# ACB_Jr_r_02.net
KiCad netlist of a schematic drawn in EAGLE
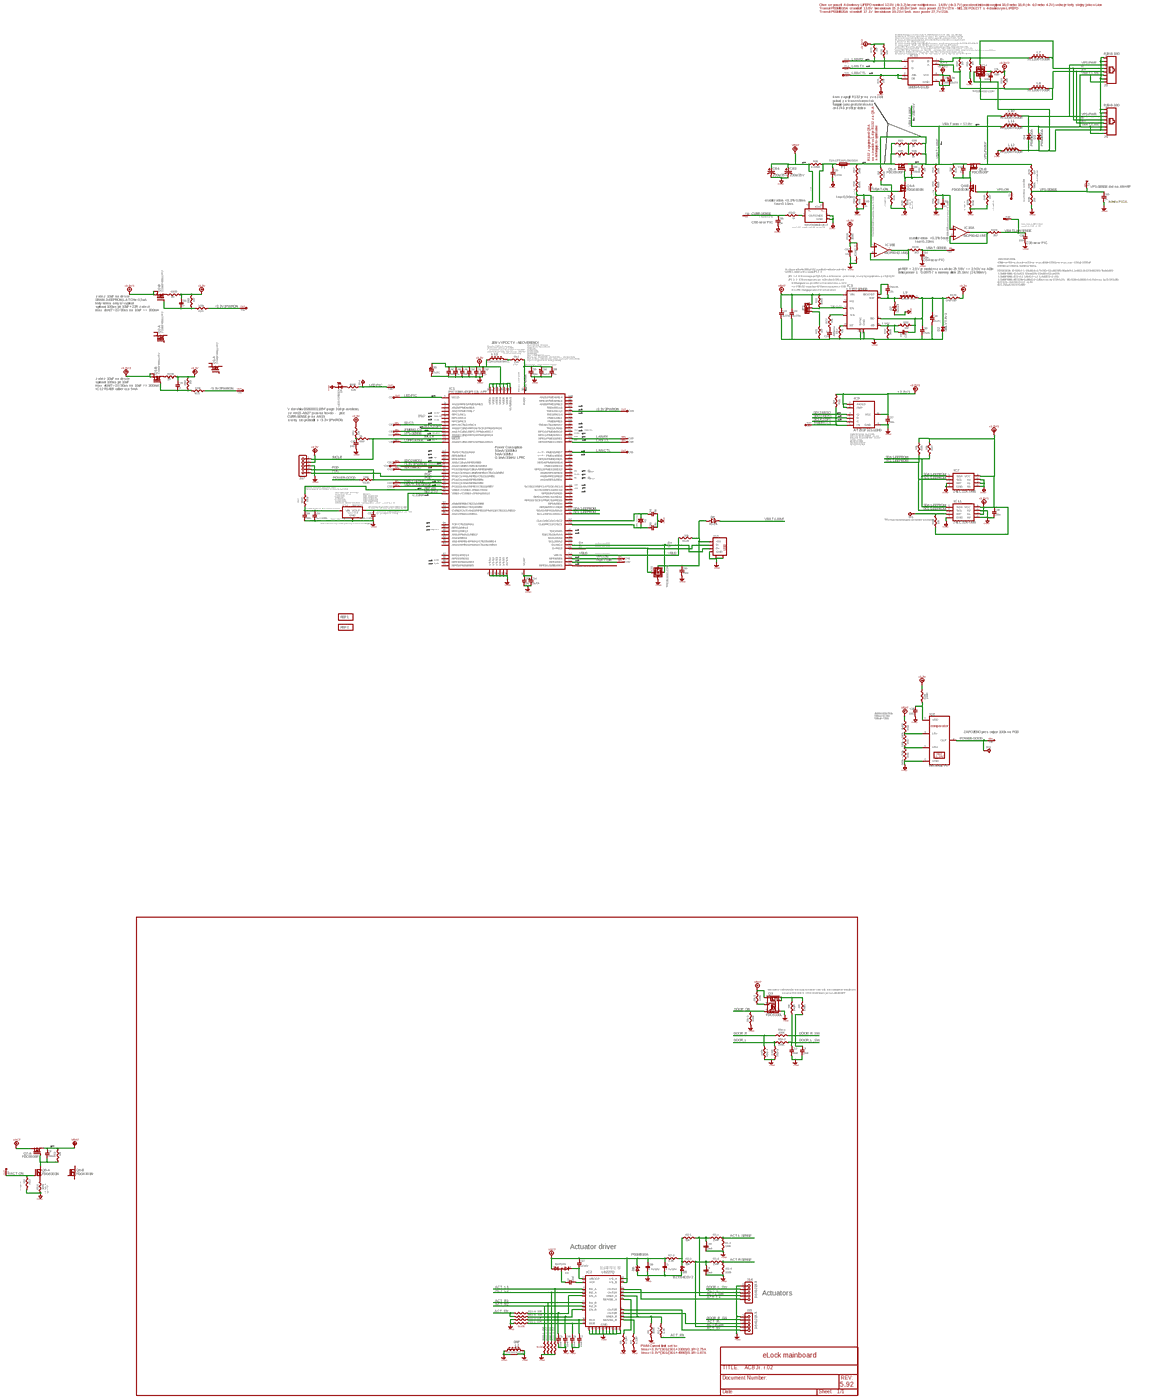
[diagram p0: schematic, sheet 1, overview]
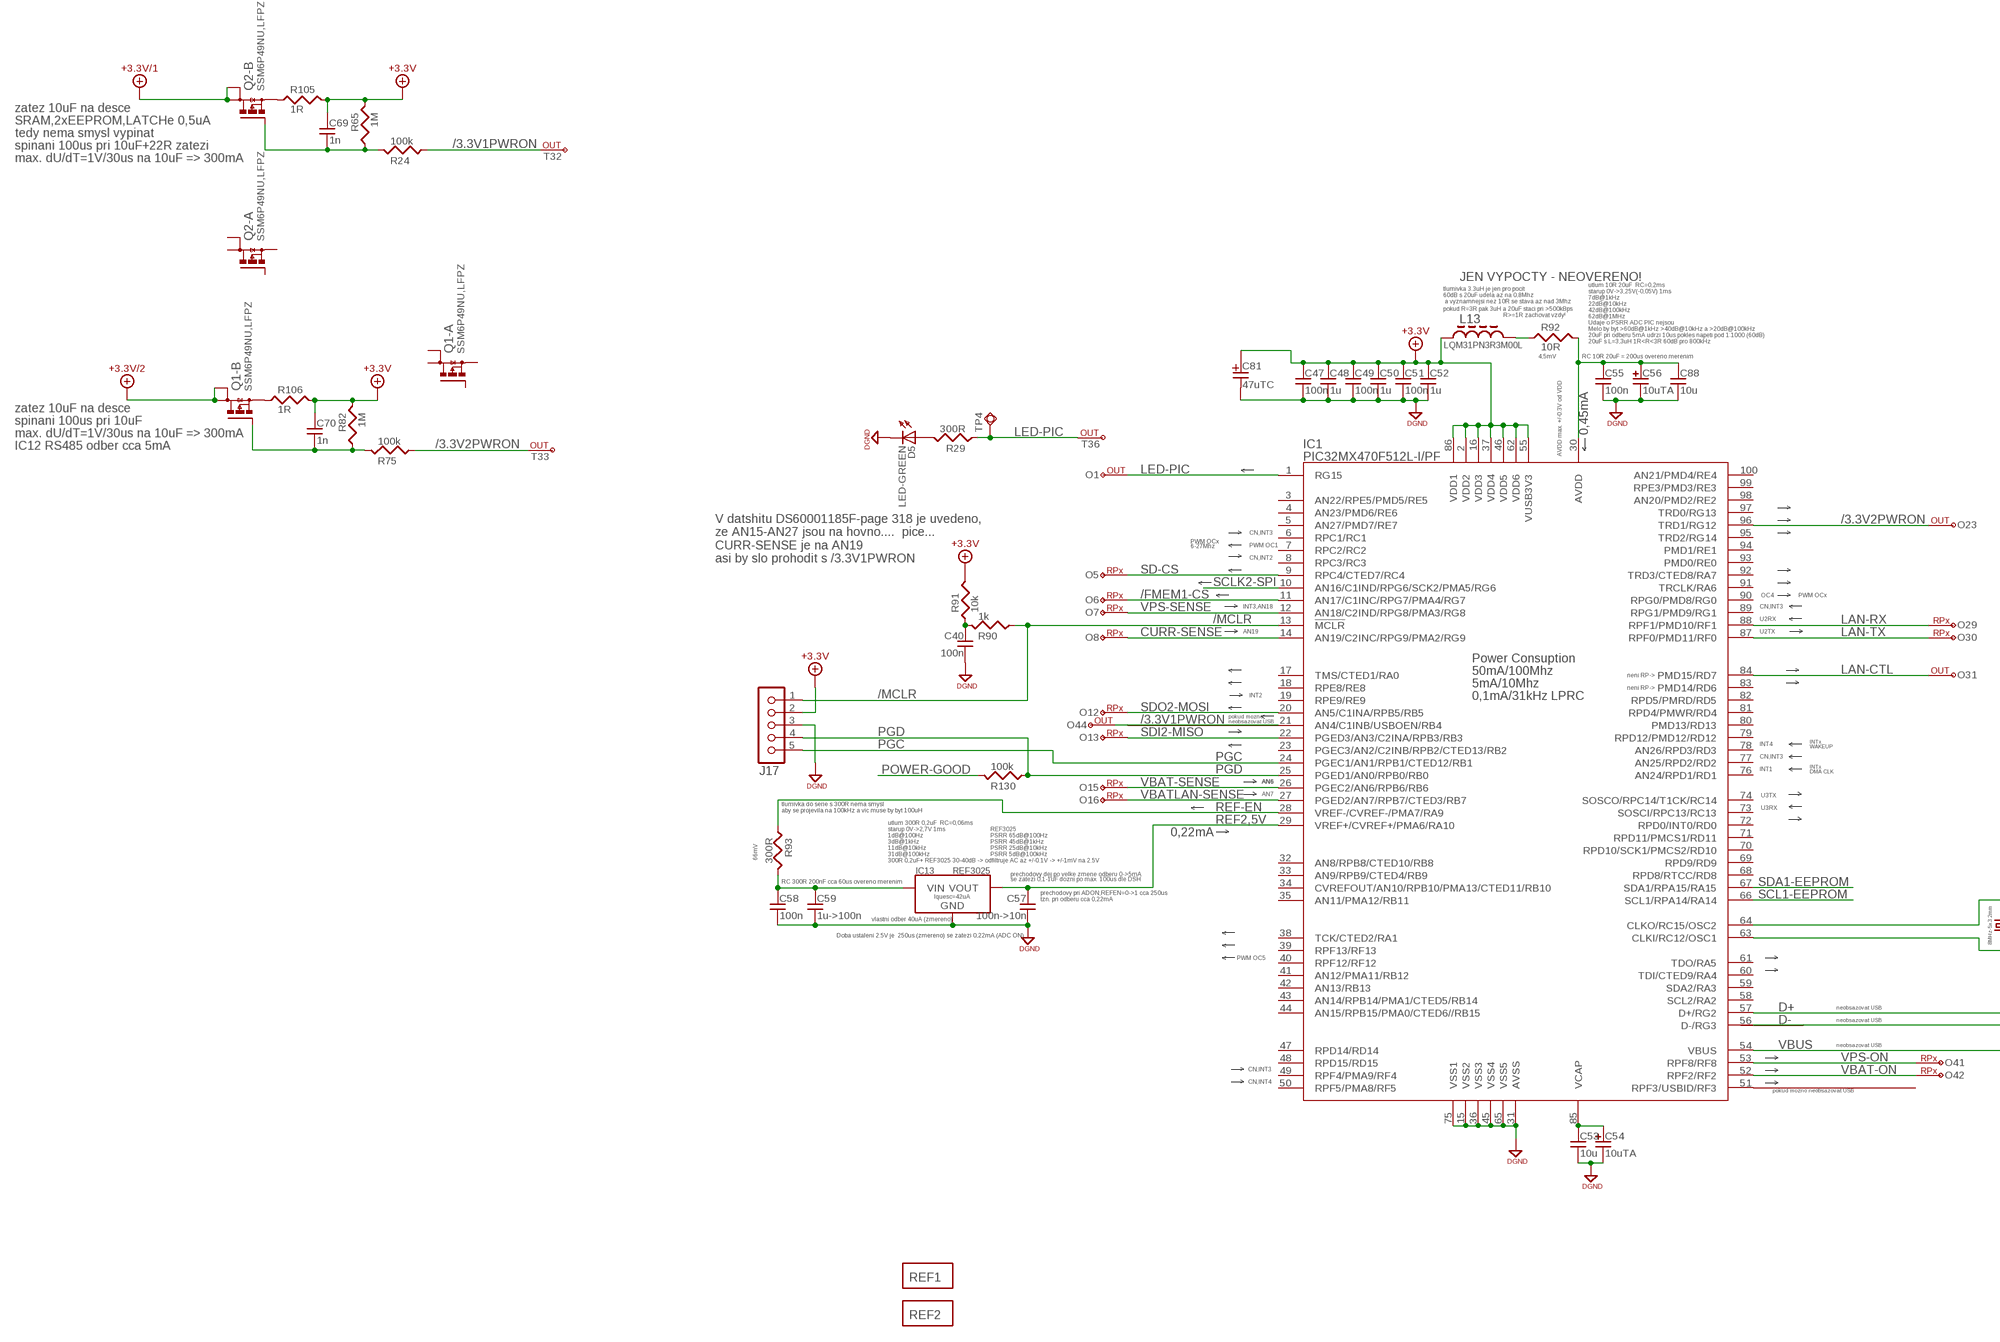
[diagram p1: schematic, sheet 1, part 1 of 5]
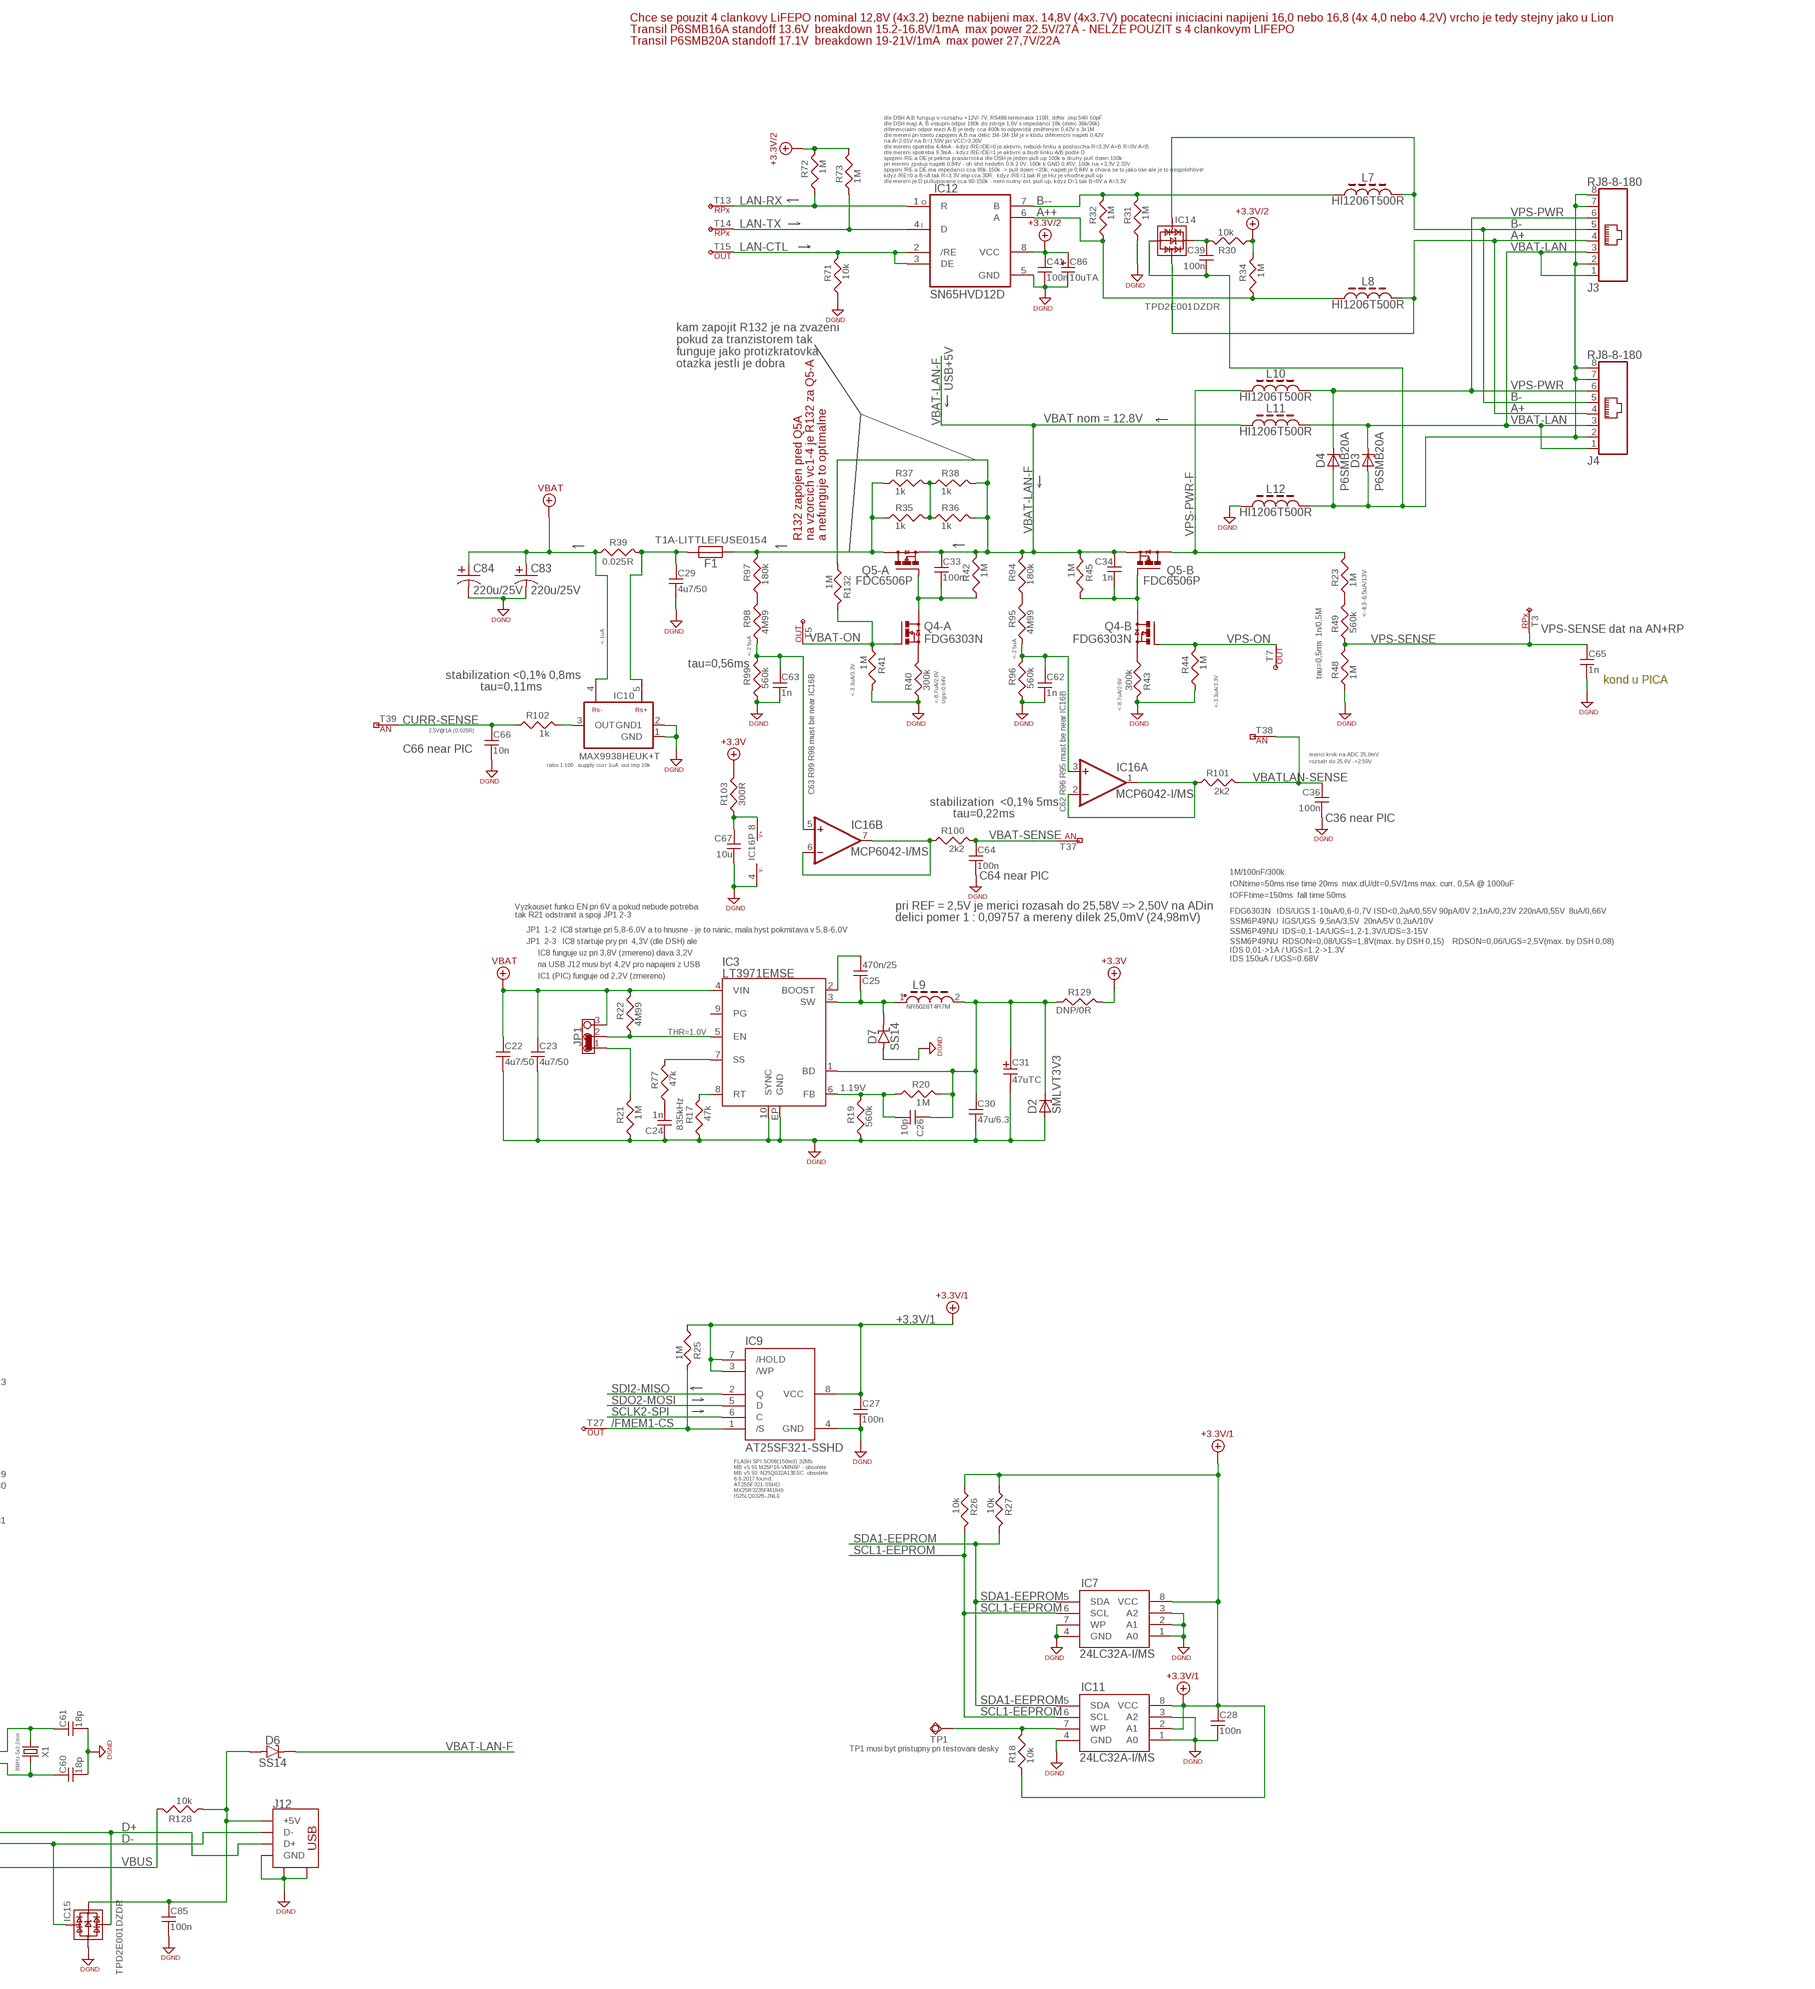
[diagram p2: schematic, sheet 1, part 2 of 5]
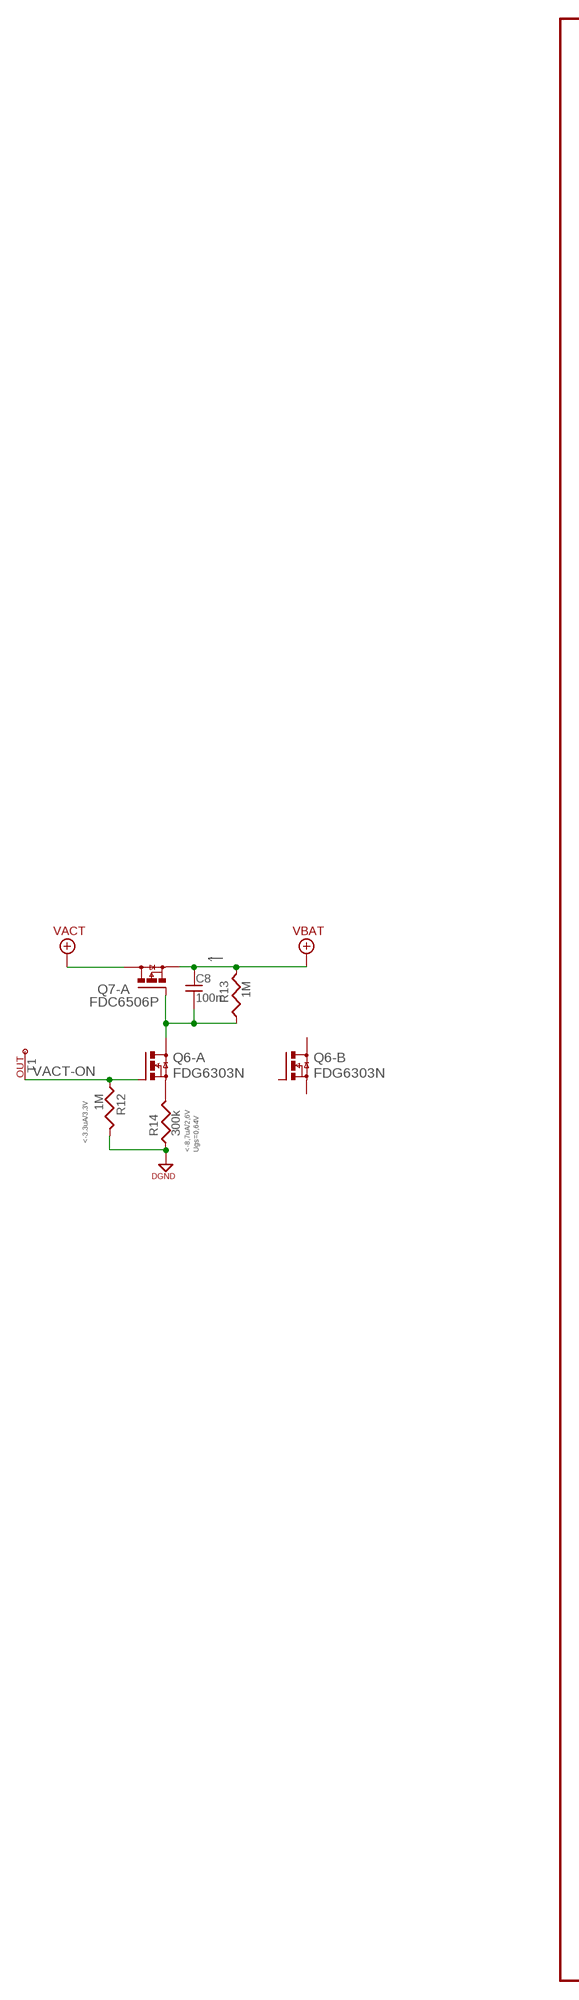
[diagram p3: schematic, sheet 1, part 3 of 5]
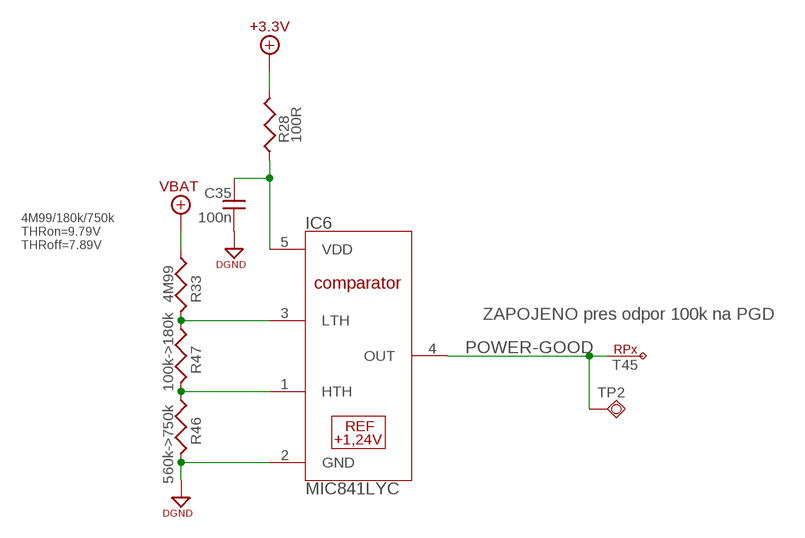
[diagram p4: schematic, sheet 1, part 4 of 5]
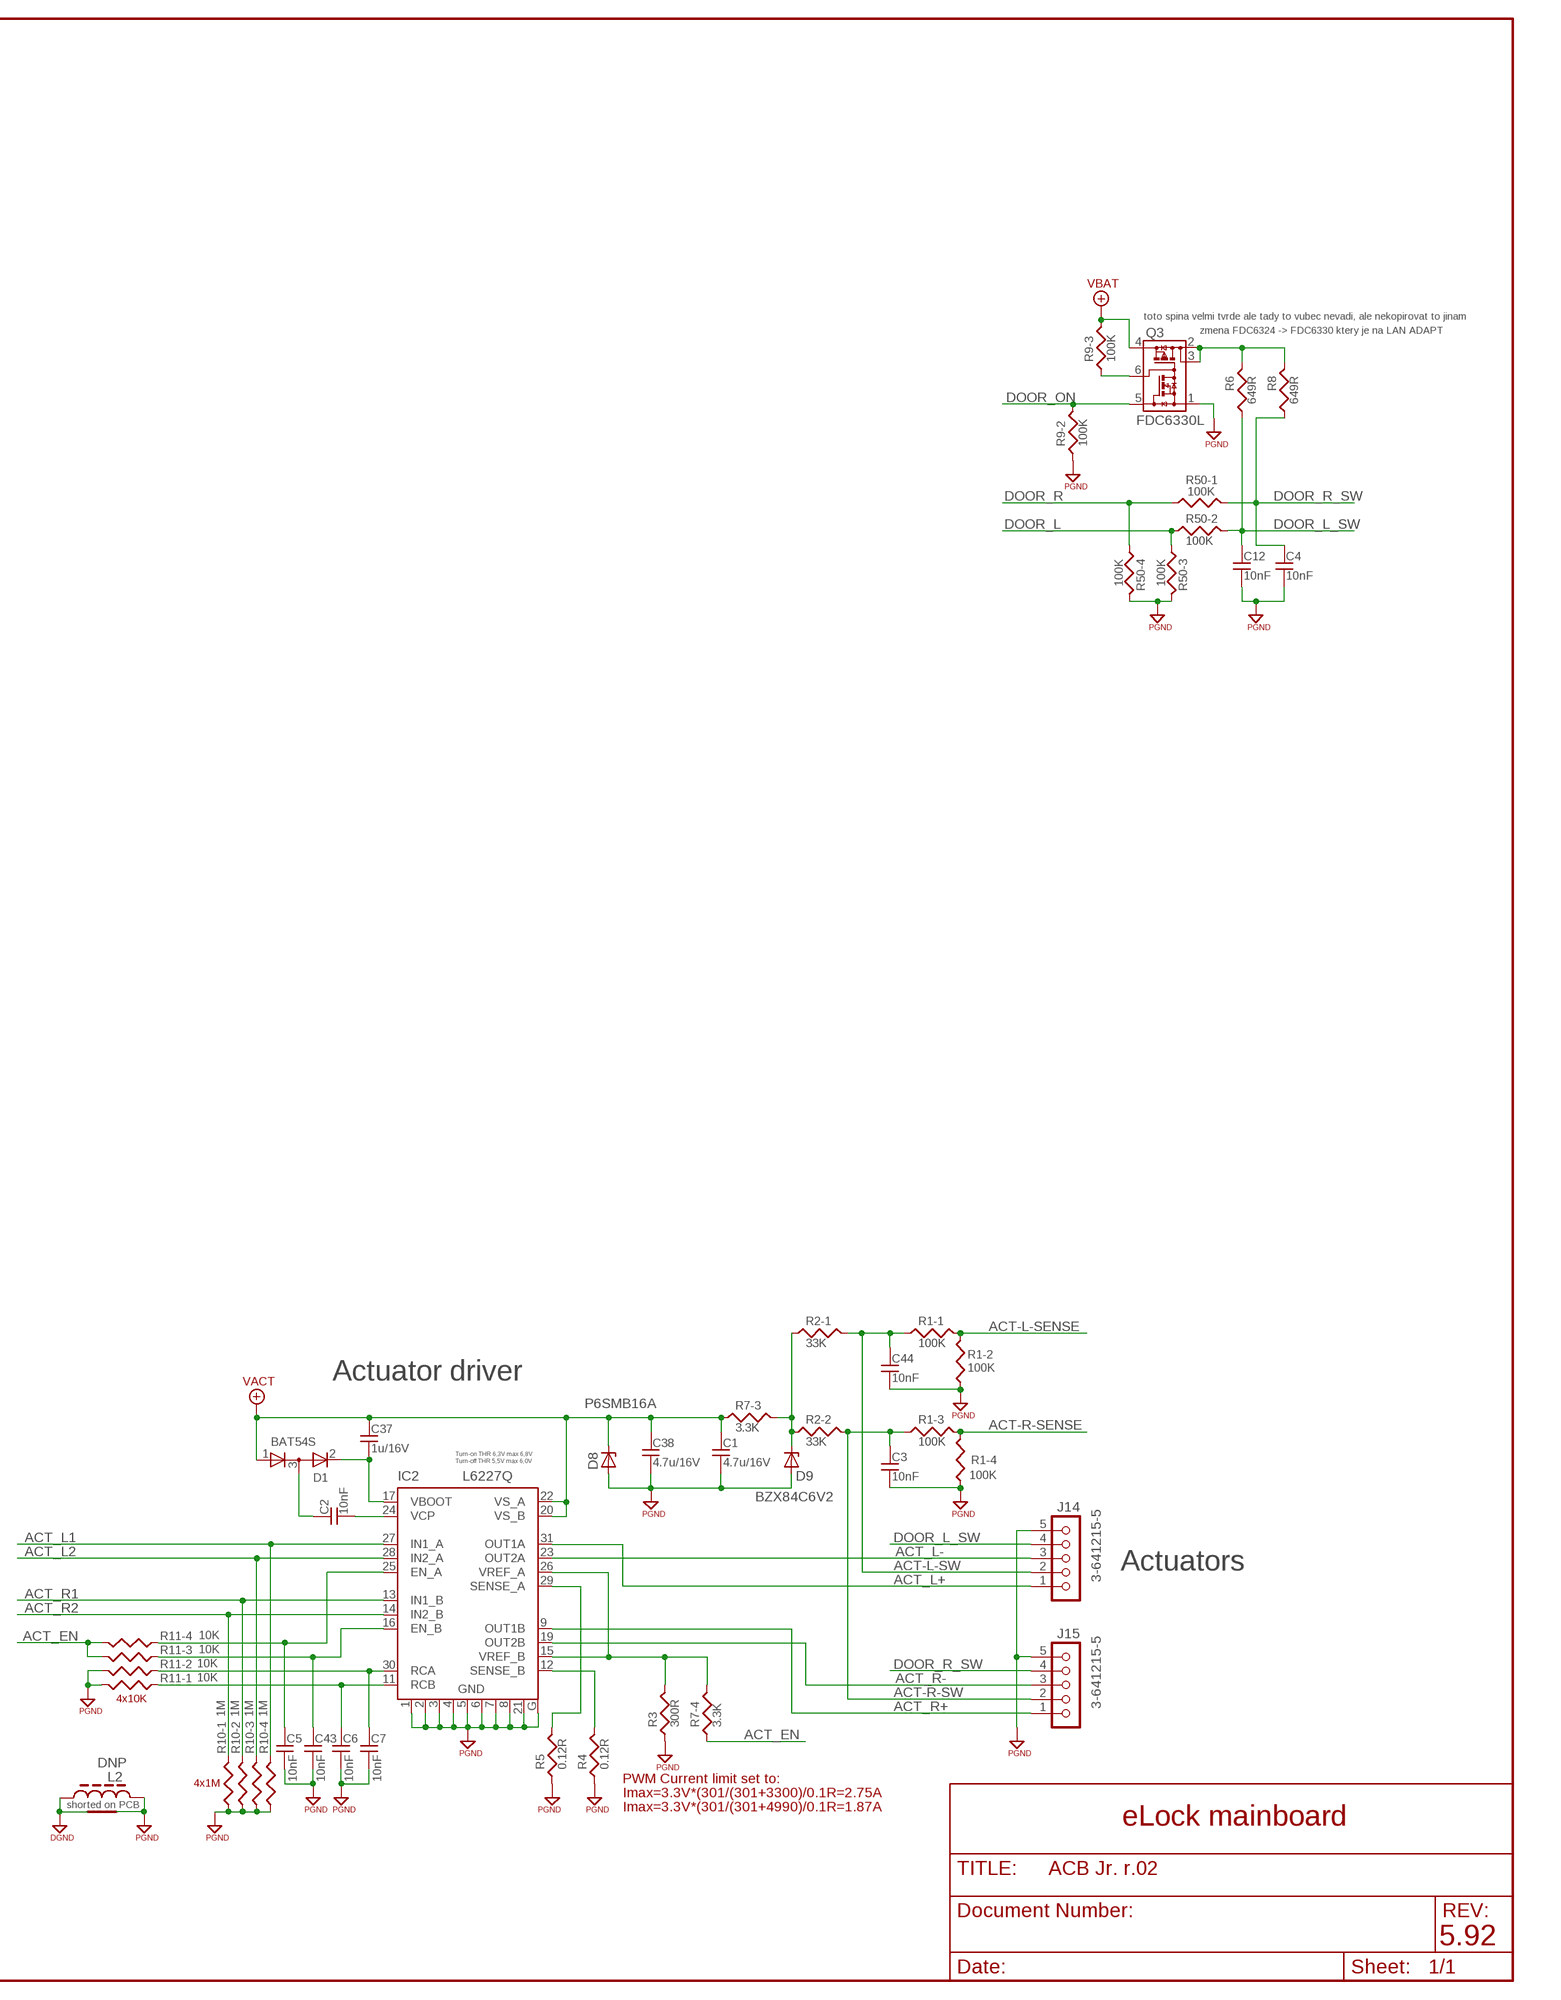
[diagram p5: schematic, sheet 1, part 5 of 5]

(export (version "E")
  (design (tool "Eeschema 10.0.6"))
  (components
    (comp (ref "C1")
      (value "4.7u/16V")
      (footprint "eagle-import:0805")
      (libsource (lib "eagle-import") (part "C-0805"))
    )
    (comp (ref "C2")
      (value "10nF")
      (footprint "eagle-import:0603")
      (libsource (lib "eagle-import") (part "C-0603"))
    )
    (comp (ref "C3")
      (value "10nF")
      (footprint "eagle-import:0603")
      (libsource (lib "eagle-import") (part "C-0603"))
    )
    (comp (ref "C4")
      (value "10nF")
      (footprint "eagle-import:0603")
      (libsource (lib "eagle-import") (part "C-0603"))
    )
    (comp (ref "C5")
      (value "10nF")
      (footprint "eagle-import:0603")
      (libsource (lib "eagle-import") (part "C-0603"))
    )
    (comp (ref "C6")
      (value "10nF")
      (footprint "eagle-import:0603")
      (libsource (lib "eagle-import") (part "C-0603"))
    )
    (comp (ref "C7")
      (value "10nF")
      (footprint "eagle-import:0603")
      (libsource (lib "eagle-import") (part "C-0603"))
    )
    (comp (ref "C8")
      (value "100n")
      (footprint "eagle-import:0603")
      (libsource (lib "eagle-import") (part "C-0603"))
    )
    (comp (ref "C12")
      (value "10nF")
      (footprint "eagle-import:0603")
      (libsource (lib "eagle-import") (part "C-0603"))
    )
    (comp (ref "C22")
      (value "4u7/50")
      (footprint "eagle-import:1206")
      (libsource (lib "eagle-import") (part "C-1206"))
    )
    (comp (ref "C23")
      (value "4u7/50")
      (footprint "eagle-import:1206")
      (libsource (lib "eagle-import") (part "C-1206"))
    )
    (comp (ref "C24")
      (value "1n")
      (footprint "eagle-import:0603")
      (libsource (lib "eagle-import") (part "C-0603"))
    )
    (comp (ref "C25")
      (value "470n/25")
      (footprint "eagle-import:0603")
      (libsource (lib "eagle-import") (part "C-0603"))
    )
    (comp (ref "C26")
      (value "10p")
      (footprint "eagle-import:0603")
      (libsource (lib "eagle-import") (part "C-0603"))
    )
    (comp (ref "C27")
      (value "100n")
      (footprint "eagle-import:0603")
      (libsource (lib "eagle-import") (part "C-0603"))
    )
    (comp (ref "C28")
      (value "100n")
      (footprint "eagle-import:0603")
      (libsource (lib "eagle-import") (part "C-0603"))
    )
    (comp (ref "C29")
      (value "4u7/50")
      (footprint "eagle-import:1206")
      (libsource (lib "eagle-import") (part "C-1206"))
    )
    (comp (ref "C30")
      (value "47u/6.3")
      (footprint "eagle-import:1206")
      (libsource (lib "eagle-import") (part "C-1206"))
    )
    (comp (ref "C31")
      (value "47uTC")
      (footprint "eagle-import:CT-C")
      (libsource (lib "eagle-import") (part "CT-C"))
    )
    (comp (ref "C33")
      (value "100n")
      (footprint "eagle-import:0603")
      (libsource (lib "eagle-import") (part "C-0603"))
    )
    (comp (ref "C34")
      (value "1n")
      (footprint "eagle-import:0603")
      (libsource (lib "eagle-import") (part "C-0603"))
    )
    (comp (ref "C35")
      (value "100n")
      (footprint "eagle-import:0603")
      (libsource (lib "eagle-import") (part "C-0603"))
    )
    (comp (ref "C36")
      (value "100n")
      (footprint "eagle-import:0603")
      (libsource (lib "eagle-import") (part "C-0603"))
    )
    (comp (ref "C37")
      (value "1u/16V")
      (footprint "eagle-import:0603")
      (libsource (lib "eagle-import") (part "C-0603"))
    )
    (comp (ref "C38")
      (value "4.7u/16V")
      (footprint "eagle-import:0805")
      (libsource (lib "eagle-import") (part "C-0805"))
    )
    (comp (ref "C39")
      (value "100n")
      (footprint "eagle-import:0603")
      (libsource (lib "eagle-import") (part "C-0603"))
    )
    (comp (ref "C40")
      (value "100n")
      (footprint "eagle-import:0603")
      (libsource (lib "eagle-import") (part "C-0603"))
    )
    (comp (ref "C41")
      (value "100n")
      (footprint "eagle-import:0603")
      (libsource (lib "eagle-import") (part "C-0603"))
    )
    (comp (ref "C43")
      (value "10nF")
      (footprint "eagle-import:0603")
      (libsource (lib "eagle-import") (part "C-0603"))
    )
    (comp (ref "C44")
      (value "10nF")
      (footprint "eagle-import:0603")
      (libsource (lib "eagle-import") (part "C-0603"))
    )
    (comp (ref "C47")
      (value "100n")
      (footprint "eagle-import:0603")
      (libsource (lib "eagle-import") (part "C-0603"))
    )
    (comp (ref "C48")
      (value "1u")
      (footprint "eagle-import:0603")
      (libsource (lib "eagle-import") (part "C-0603"))
    )
    (comp (ref "C49")
      (value "100n")
      (footprint "eagle-import:0603")
      (libsource (lib "eagle-import") (part "C-0603"))
    )
    (comp (ref "C50")
      (value "1u")
      (footprint "eagle-import:0603")
      (libsource (lib "eagle-import") (part "C-0603"))
    )
    (comp (ref "C51")
      (value "100n")
      (footprint "eagle-import:0603")
      (libsource (lib "eagle-import") (part "C-0603"))
    )
    (comp (ref "C52")
      (value "1u")
      (footprint "eagle-import:0603")
      (libsource (lib "eagle-import") (part "C-0603"))
    )
    (comp (ref "C53")
      (value "10u")
      (footprint "eagle-import:0603")
      (libsource (lib "eagle-import") (part "C-0603"))
    )
    (comp (ref "C54")
      (value "10uTA")
      (footprint "eagle-import:1206-POL-C")
      (libsource (lib "eagle-import") (part "CT-1206"))
    )
    (comp (ref "C55")
      (value "100n")
      (footprint "eagle-import:0603")
      (libsource (lib "eagle-import") (part "C-0603"))
    )
    (comp (ref "C56")
      (value "10uTA")
      (footprint "eagle-import:1206-POL-C")
      (libsource (lib "eagle-import") (part "CT-1206"))
    )
    (comp (ref "C57")
      (value "100n->10n")
      (footprint "eagle-import:0603")
      (libsource (lib "eagle-import") (part "C-0603"))
    )
    (comp (ref "C58")
      (value "100n")
      (footprint "eagle-import:0603")
      (libsource (lib "eagle-import") (part "C-0603"))
    )
    (comp (ref "C59")
      (value "1u->100n")
      (footprint "eagle-import:0603")
      (libsource (lib "eagle-import") (part "C-0603"))
    )
    (comp (ref "C60")
      (value "18p")
      (footprint "eagle-import:0603")
      (libsource (lib "eagle-import") (part "C-0603"))
    )
    (comp (ref "C61")
      (value "18p")
      (footprint "eagle-import:0603")
      (libsource (lib "eagle-import") (part "C-0603"))
    )
    (comp (ref "C62")
      (value "1n")
      (footprint "eagle-import:0603")
      (libsource (lib "eagle-import") (part "C-0603"))
    )
    (comp (ref "C63")
      (value "1n")
      (footprint "eagle-import:0603")
      (libsource (lib "eagle-import") (part "C-0603"))
    )
    (comp (ref "C64")
      (value "100n")
      (footprint "eagle-import:0603")
      (libsource (lib "eagle-import") (part "C-0603"))
    )
    (comp (ref "C65")
      (value "1n")
      (footprint "eagle-import:0603")
      (libsource (lib "eagle-import") (part "C-0603"))
    )
    (comp (ref "C66")
      (value "10n")
      (footprint "eagle-import:0603")
      (libsource (lib "eagle-import") (part "C-0603"))
    )
    (comp (ref "C67")
      (value "10u")
      (footprint "eagle-import:0603")
      (libsource (lib "eagle-import") (part "C-0603"))
    )
    (comp (ref "C69")
      (value "1n")
      (footprint "eagle-import:0603")
      (libsource (lib "eagle-import") (part "C-0603"))
    )
    (comp (ref "C70")
      (value "1n")
      (footprint "eagle-import:0603")
      (libsource (lib "eagle-import") (part "C-0603"))
    )
    (comp (ref "C81")
      (value "47uTC")
      (footprint "eagle-import:CT-C")
      (libsource (lib "eagle-import") (part "CT-C"))
    )
    (comp (ref "C83")
      (value "220u/25V")
      (footprint "eagle-import:CAP_8MM_DIA_SMT")
      (libsource (lib "eagle-import") (part "CAP-ELEC-SMD-8MM"))
    )
    (comp (ref "C84")
      (value "220u/25V")
      (footprint "eagle-import:CAP_8MM_DIA_SMT")
      (libsource (lib "eagle-import") (part "CAP-ELEC-SMD-8MM"))
    )
    (comp (ref "C85")
      (value "100n")
      (footprint "eagle-import:0603")
      (libsource (lib "eagle-import") (part "C-0603"))
    )
    (comp (ref "C86")
      (value "10uTA")
      (footprint "eagle-import:1206-POL-C")
      (libsource (lib "eagle-import") (part "CT-1206"))
    )
    (comp (ref "C88")
      (value "10u")
      (footprint "eagle-import:0603")
      (libsource (lib "eagle-import") (part "C-0603"))
    )
    (comp (ref "D1")
      (value "BAT54S")
      (footprint "eagle-import:SOT-23")
      (libsource (lib "eagle-import") (part "BAT54S"))
    )
    (comp (ref "D2")
      (value "SMLVT3V3")
      (footprint "eagle-import:SMA")
      (libsource (lib "eagle-import") (part "SMLVT3V3"))
    )
    (comp (ref "D3")
      (value "P6SMB20A")
      (footprint "eagle-import:SMB")
      (libsource (lib "eagle-import") (part "P6SMB"))
    )
    (comp (ref "D4")
      (value "P6SMB20A")
      (footprint "eagle-import:SMB")
      (libsource (lib "eagle-import") (part "P6SMB"))
    )
    (comp (ref "D5")
      (value "LED-GREEN")
      (footprint "eagle-import:0805-POL-D")
      (libsource (lib "eagle-import") (part "LED-0805"))
    )
    (comp (ref "D6")
      (value "SS14")
      (footprint "eagle-import:SMA")
      (libsource (lib "eagle-import") (part "DS-SMA"))
    )
    (comp (ref "D7")
      (value "SS14")
      (footprint "eagle-import:SMA")
      (libsource (lib "eagle-import") (part "DS-SMA"))
    )
    (comp (ref "D8")
      (value "P6SMB16A")
      (footprint "eagle-import:SMB")
      (libsource (lib "eagle-import") (part "P6SMB"))
    )
    (comp (ref "D9")
      (value "BZX84C6V2")
      (footprint "eagle-import:SOT-23")
      (libsource (lib "eagle-import") (part "BZX84C6V2"))
    )
    (comp (ref "F1")
      (value "T1A-LITTLEFUSE0154")
      (footprint "eagle-import:LITTLEFUSE0154")
      (libsource (lib "eagle-import") (part "POJISTKA-LITTLEFUSE0154"))
    )
    (comp (ref "IC1")
      (value "PIC32MX470F512L-I/PF")
      (footprint "eagle-import:TQFP100_14X14_0,5MM")
      (libsource (lib "eagle-import") (part "PIC32MX470F512L-I/PF"))
    )
    (comp (ref "IC2")
      (value "L6227Q")
      (footprint "eagle-import:SQFP-S-5X5-32")
      (libsource (lib "eagle-import") (part "L6227Q"))
    )
    (comp (ref "IC3")
      (value "LT3971EMSE")
      (footprint "eagle-import:MSOP10EXP")
      (libsource (lib "eagle-import") (part "LT3971EMSE"))
    )
    (comp (ref "IC6")
      (value "MIC841LYC")
      (footprint "eagle-import:SC-70-5")
      (libsource (lib "eagle-import") (part "MIC841LYC"))
    )
    (comp (ref "IC7")
      (value "24LC32A-I/MS")
      (footprint "eagle-import:MSOP-08")
      (libsource (lib "eagle-import") (part "24-I/MS"))
    )
    (comp (ref "IC9")
      (value "AT25SF321-SSHD")
      (footprint "eagle-import:SO-08")
      (libsource (lib "eagle-import") (part "M25P16-VMN6P"))
    )
    (comp (ref "IC10")
      (value "MAX9938HEUK+T")
      (footprint "eagle-import:SOT23-5")
      (libsource (lib "eagle-import") (part "TSM9938HEUK+T"))
    )
    (comp (ref "IC11")
      (value "24LC32A-I/MS")
      (footprint "eagle-import:MSOP-08")
      (libsource (lib "eagle-import") (part "24-I/MS"))
    )
    (comp (ref "IC12")
      (value "SN65HVD12D")
      (footprint "eagle-import:SO08")
      (libsource (lib "eagle-import") (part "SN65HVD3082ED"))
    )
    (comp (ref "IC13")
      (value "REF3025")
      (footprint "eagle-import:SOT23")
      (libsource (lib "eagle-import") (part "REF3025"))
    )
    (comp (ref "IC14")
      (value "TPD2E001DZDR")
      (footprint "eagle-import:SOT-143")
      (libsource (lib "eagle-import") (part "SR05.TCT"))
    )
    (comp (ref "IC15")
      (value "TPD2E001DZDR")
      (footprint "eagle-import:SOT-143")
      (libsource (lib "eagle-import") (part "SR05.TCT"))
    )
    (comp (ref "IC16")
      (value "MCP6042-I/MS")
      (footprint "eagle-import:MSOP-08")
      (libsource (lib "eagle-import") (part "MCP6042-I/MS"))
    )
    (comp (ref "J3")
      (value "RJ8-8-180")
      (footprint "eagle-import:RJ8-8-180")
      (libsource (lib "eagle-import") (part "RJ8-8-180"))
    )
    (comp (ref "J4")
      (value "RJ8-8-180")
      (footprint "eagle-import:RJ8-8-180")
      (libsource (lib "eagle-import") (part "RJ8-8-180"))
    )
    (comp (ref "J12")
      (value "USB_A_180")
      (footprint "eagle-import:USB_B_180")
      (libsource (lib "eagle-import") (part "USB_B_180"))
    )
    (comp (ref "J14")
      (value "3-641215-5")
      (footprint "eagle-import:3-641215-5")
      (libsource (lib "eagle-import") (part "3-641215-5"))
    )
    (comp (ref "J15")
      (value "3-641215-5")
      (footprint "eagle-import:3-641215-5")
      (libsource (lib "eagle-import") (part "3-641215-5"))
    )
    (comp (ref "J17")
      (value "DNP-open-hole")
      (footprint "eagle-import:MA05-1")
      (libsource (lib "eagle-import") (part "MA05-1"))
    )
    (comp (ref "JP1")
      (value "JP3CLOSE12")
      (footprint "eagle-import:JP3CLOSE12")
      (libsource (lib "eagle-import") (part "JP3CLOSE12"))
    )
    (comp (ref "L2")
      (value "DNP")
      (footprint "eagle-import:0805-0RTOP")
      (libsource (lib "eagle-import") (part "L-0805-0R"))
    )
    (comp (ref "L7")
      (value "HI1206T500R")
      (footprint "eagle-import:1206")
      (libsource (lib "eagle-import") (part "L-1206"))
    )
    (comp (ref "L8")
      (value "HI1206T500R")
      (footprint "eagle-import:1206")
      (libsource (lib "eagle-import") (part "L-1206"))
    )
    (comp (ref "L9")
      (value "NR6028T4R7M")
      (footprint "eagle-import:NR6028")
      (libsource (lib "eagle-import") (part "NR6028"))
    )
    (comp (ref "L10")
      (value "HI1206T500R")
      (footprint "eagle-import:1206")
      (libsource (lib "eagle-import") (part "L-1206"))
    )
    (comp (ref "L11")
      (value "HI1206T500R")
      (footprint "eagle-import:1206")
      (libsource (lib "eagle-import") (part "L-1206"))
    )
    (comp (ref "L12")
      (value "HI1206T500R")
      (footprint "eagle-import:1206")
      (libsource (lib "eagle-import") (part "L-1206"))
    )
    (comp (ref "L13")
      (value "LQM31PN3R3M00L")
      (footprint "eagle-import:1206")
      (libsource (lib "eagle-import") (part "L-1206"))
    )
    (comp (ref "O1")
      (value "PIC-OUT")
      (footprint "eagle-import:TEMP-PAD")
      (libsource (lib "eagle-import") (part "PIC-OUT"))
    )
    (comp (ref "O5")
      (value "PIC-RPX")
      (footprint "eagle-import:TEMP-PAD")
      (libsource (lib "eagle-import") (part "PIC-RPX"))
    )
    (comp (ref "O6")
      (value "PIC-RPX")
      (footprint "eagle-import:TEMP-PAD")
      (libsource (lib "eagle-import") (part "PIC-RPX"))
    )
    (comp (ref "O7")
      (value "PIC-RPX")
      (footprint "eagle-import:TEMP-PAD")
      (libsource (lib "eagle-import") (part "PIC-RPX"))
    )
    (comp (ref "O8")
      (value "PIC-RPX")
      (footprint "eagle-import:TEMP-PAD")
      (libsource (lib "eagle-import") (part "PIC-RPX"))
    )
    (comp (ref "O12")
      (value "PIC-RPX")
      (footprint "eagle-import:TEMP-PAD")
      (libsource (lib "eagle-import") (part "PIC-RPX"))
    )
    (comp (ref "O13")
      (value "PIC-RPX")
      (footprint "eagle-import:TEMP-PAD")
      (libsource (lib "eagle-import") (part "PIC-RPX"))
    )
    (comp (ref "O15")
      (value "PIC-RPX")
      (footprint "eagle-import:TEMP-PAD")
      (libsource (lib "eagle-import") (part "PIC-RPX"))
    )
    (comp (ref "O16")
      (value "PIC-RPX")
      (footprint "eagle-import:TEMP-PAD")
      (libsource (lib "eagle-import") (part "PIC-RPX"))
    )
    (comp (ref "O23")
      (value "PIC-OUT")
      (footprint "eagle-import:TEMP-PAD")
      (libsource (lib "eagle-import") (part "PIC-OUT"))
    )
    (comp (ref "O29")
      (value "PIC-RPX")
      (footprint "eagle-import:TEMP-PAD")
      (libsource (lib "eagle-import") (part "PIC-RPX"))
    )
    (comp (ref "O30")
      (value "PIC-RPX")
      (footprint "eagle-import:TEMP-PAD")
      (libsource (lib "eagle-import") (part "PIC-RPX"))
    )
    (comp (ref "O31")
      (value "PIC-OUT")
      (footprint "eagle-import:TEMP-PAD")
      (libsource (lib "eagle-import") (part "PIC-OUT"))
    )
    (comp (ref "O41")
      (value "PIC-RPX")
      (footprint "eagle-import:TEMP-PAD")
      (libsource (lib "eagle-import") (part "PIC-RPX"))
    )
    (comp (ref "O42")
      (value "PIC-RPX")
      (footprint "eagle-import:TEMP-PAD")
      (libsource (lib "eagle-import") (part "PIC-RPX"))
    )
    (comp (ref "O44")
      (value "PIC-OUT")
      (footprint "eagle-import:TEMP-PAD")
      (libsource (lib "eagle-import") (part "PIC-OUT"))
    )
    (comp (ref "Q1")
      (value "SSM6P49NU,LFPZ")
      (footprint "eagle-import:MICRO_FET")
      (libsource (lib "eagle-import") (part "SSM6P49PZNU,LF"))
    )
    (comp (ref "Q2")
      (value "SSM6P49NU,LFPZ")
      (footprint "eagle-import:MICRO_FET")
      (libsource (lib "eagle-import") (part "SSM6P49PZNU,LF"))
    )
    (comp (ref "Q3")
      (value "FDC6330L")
      (footprint "eagle-import:SSOT-6")
      (libsource (lib "eagle-import") (part "FDC6330L"))
    )
    (comp (ref "Q4")
      (value "FDG6303N")
      (footprint "eagle-import:SC70-6")
      (libsource (lib "eagle-import") (part "FDG6303N"))
    )
    (comp (ref "Q5")
      (value "FDC6506P")
      (footprint "eagle-import:SSOT-6")
      (libsource (lib "eagle-import") (part "FDC6506D"))
    )
    (comp (ref "Q6")
      (value "FDG6303N")
      (footprint "eagle-import:SC70-6")
      (libsource (lib "eagle-import") (part "FDG6303N"))
    )
    (comp (ref "Q7")
      (value "FDC6506P")
      (footprint "eagle-import:SSOT-6")
      (libsource (lib "eagle-import") (part "FDC6506D"))
    )
    (comp (ref "R1")
      (value "100K")
      (footprint "eagle-import:0603-ARRAY")
      (libsource (lib "eagle-import") (part "EXB-38"))
    )
    (comp (ref "R2")
      (value "33K")
      (footprint "eagle-import:0603-ARRAY")
      (libsource (lib "eagle-import") (part "EXB-38"))
    )
    (comp (ref "R3")
      (value "300R")
      (footprint "eagle-import:0603")
      (libsource (lib "eagle-import") (part "R-0603"))
    )
    (comp (ref "R4")
      (value "0.12R")
      (footprint "eagle-import:0805")
      (libsource (lib "eagle-import") (part "R-0805"))
    )
    (comp (ref "R5")
      (value "0.12R")
      (footprint "eagle-import:0805")
      (libsource (lib "eagle-import") (part "R-0805"))
    )
    (comp (ref "R6")
      (value "649R")
      (footprint "eagle-import:0603")
      (libsource (lib "eagle-import") (part "R-0603"))
    )
    (comp (ref "R7")
      (value "3.3K")
      (footprint "eagle-import:0603-ARRAY")
      (libsource (lib "eagle-import") (part "EXB-38"))
    )
    (comp (ref "R8")
      (value "649R")
      (footprint "eagle-import:0603")
      (libsource (lib "eagle-import") (part "R-0603"))
    )
    (comp (ref "R9")
      (value "100K")
      (footprint "eagle-import:0603-ARRAY")
      (libsource (lib "eagle-import") (part "EXB-38"))
    )
    (comp (ref "R10")
      (value "1M")
      (footprint "eagle-import:0603-ARRAY")
      (libsource (lib "eagle-import") (part "EXB-38"))
    )
    (comp (ref "R11")
      (value "10K")
      (footprint "eagle-import:0603-ARRAY")
      (libsource (lib "eagle-import") (part "EXB-38"))
    )
    (comp (ref "R12")
      (value "1M")
      (footprint "eagle-import:0603")
      (libsource (lib "eagle-import") (part "R-0603"))
    )
    (comp (ref "R13")
      (value "1M")
      (footprint "eagle-import:0603")
      (libsource (lib "eagle-import") (part "R-0603"))
    )
    (comp (ref "R14")
      (value "300k")
      (footprint "eagle-import:0603")
      (libsource (lib "eagle-import") (part "R-0603"))
    )
    (comp (ref "R17")
      (value "47k")
      (footprint "eagle-import:0603")
      (libsource (lib "eagle-import") (part "R-0603"))
    )
    (comp (ref "R18")
      (value "10k")
      (footprint "eagle-import:0603")
      (libsource (lib "eagle-import") (part "R-0603"))
    )
    (comp (ref "R19")
      (value "560k")
      (footprint "eagle-import:0603")
      (libsource (lib "eagle-import") (part "R-0603"))
    )
    (comp (ref "R20")
      (value "1M")
      (footprint "eagle-import:0603")
      (libsource (lib "eagle-import") (part "R-0603"))
    )
    (comp (ref "R21")
      (value "1M")
      (footprint "eagle-import:0603")
      (libsource (lib "eagle-import") (part "R-0603"))
    )
    (comp (ref "R22")
      (value "4M99")
      (footprint "eagle-import:0603")
      (libsource (lib "eagle-import") (part "R-0603"))
    )
    (comp (ref "R23")
      (value "1M")
      (footprint "eagle-import:0603")
      (libsource (lib "eagle-import") (part "R-0603"))
    )
    (comp (ref "R24")
      (value "100k")
      (footprint "eagle-import:0603")
      (libsource (lib "eagle-import") (part "R-0603"))
    )
    (comp (ref "R25")
      (value "1M")
      (footprint "eagle-import:0603")
      (libsource (lib "eagle-import") (part "R-0603"))
    )
    (comp (ref "R26")
      (value "10k")
      (footprint "eagle-import:0603")
      (libsource (lib "eagle-import") (part "R-0603"))
    )
    (comp (ref "R27")
      (value "10k")
      (footprint "eagle-import:0603")
      (libsource (lib "eagle-import") (part "R-0603"))
    )
    (comp (ref "R28")
      (value "100R")
      (footprint "eagle-import:0603")
      (libsource (lib "eagle-import") (part "R-0603"))
    )
    (comp (ref "R29")
      (value "300R")
      (footprint "eagle-import:0603")
      (libsource (lib "eagle-import") (part "R-0603"))
    )
    (comp (ref "R30")
      (value "10k")
      (footprint "eagle-import:0603")
      (libsource (lib "eagle-import") (part "R-0603"))
    )
    (comp (ref "R31")
      (value "1M")
      (footprint "eagle-import:0603")
      (libsource (lib "eagle-import") (part "R-0603"))
    )
    (comp (ref "R32")
      (value "1M")
      (footprint "eagle-import:0603")
      (libsource (lib "eagle-import") (part "R-0603"))
    )
    (comp (ref "R33")
      (value "4M99")
      (footprint "eagle-import:0603")
      (libsource (lib "eagle-import") (part "R-0603"))
    )
    (comp (ref "R34")
      (value "1M")
      (footprint "eagle-import:0603")
      (libsource (lib "eagle-import") (part "R-0603"))
    )
    (comp (ref "R35")
      (value "1k")
      (footprint "eagle-import:0805")
      (libsource (lib "eagle-import") (part "R-0805"))
    )
    (comp (ref "R36")
      (value "1k")
      (footprint "eagle-import:0805")
      (libsource (lib "eagle-import") (part "R-0805"))
    )
    (comp (ref "R37")
      (value "1k")
      (footprint "eagle-import:0805")
      (libsource (lib "eagle-import") (part "R-0805"))
    )
    (comp (ref "R38")
      (value "1k")
      (footprint "eagle-import:0805")
      (libsource (lib "eagle-import") (part "R-0805"))
    )
    (comp (ref "R39")
      (value "0.025R")
      (footprint "eagle-import:0805")
      (libsource (lib "eagle-import") (part "R-0805"))
    )
    (comp (ref "R40")
      (value "300k")
      (footprint "eagle-import:0603")
      (libsource (lib "eagle-import") (part "R-0603"))
    )
    (comp (ref "R41")
      (value "1M")
      (footprint "eagle-import:0603")
      (libsource (lib "eagle-import") (part "R-0603"))
    )
    (comp (ref "R42")
      (value "1M")
      (footprint "eagle-import:0603")
      (libsource (lib "eagle-import") (part "R-0603"))
    )
    (comp (ref "R43")
      (value "300k")
      (footprint "eagle-import:0603")
      (libsource (lib "eagle-import") (part "R-0603"))
    )
    (comp (ref "R44")
      (value "1M")
      (footprint "eagle-import:0603")
      (libsource (lib "eagle-import") (part "R-0603"))
    )
    (comp (ref "R45")
      (value "1M")
      (footprint "eagle-import:0603")
      (libsource (lib "eagle-import") (part "R-0603"))
    )
    (comp (ref "R46")
      (value "560k->750k")
      (footprint "eagle-import:0603")
      (libsource (lib "eagle-import") (part "R-0603"))
    )
    (comp (ref "R47")
      (value "100k->180k")
      (footprint "eagle-import:0603")
      (libsource (lib "eagle-import") (part "R-0603"))
    )
    (comp (ref "R48")
      (value "1M")
      (footprint "eagle-import:0603")
      (libsource (lib "eagle-import") (part "R-0603"))
    )
    (comp (ref "R49")
      (value "560k")
      (footprint "eagle-import:0603")
      (libsource (lib "eagle-import") (part "R-0603"))
    )
    (comp (ref "R50")
      (value "100K")
      (footprint "eagle-import:0603-ARRAY")
      (libsource (lib "eagle-import") (part "EXB-38"))
    )
    (comp (ref "R65")
      (value "1M")
      (footprint "eagle-import:0603")
      (libsource (lib "eagle-import") (part "R-0603"))
    )
    (comp (ref "R71")
      (value "10k")
      (footprint "eagle-import:0603")
      (libsource (lib "eagle-import") (part "R-0603"))
    )
    (comp (ref "R72")
      (value "1M")
      (footprint "eagle-import:0603")
      (libsource (lib "eagle-import") (part "R-0603"))
    )
    (comp (ref "R73")
      (value "1M")
      (footprint "eagle-import:0603")
      (libsource (lib "eagle-import") (part "R-0603"))
    )
    (comp (ref "R75")
      (value "100k")
      (footprint "eagle-import:0603")
      (libsource (lib "eagle-import") (part "R-0603"))
    )
    (comp (ref "R77")
      (value "47k")
      (footprint "eagle-import:0603")
      (libsource (lib "eagle-import") (part "R-0603"))
    )
    (comp (ref "R82")
      (value "1M")
      (footprint "eagle-import:0603")
      (libsource (lib "eagle-import") (part "R-0603"))
    )
    (comp (ref "R90")
      (value "1k")
      (footprint "eagle-import:0603")
      (libsource (lib "eagle-import") (part "R-0603"))
    )
    (comp (ref "R91")
      (value "10k")
      (footprint "eagle-import:0603")
      (libsource (lib "eagle-import") (part "R-0603"))
    )
    (comp (ref "R92")
      (value "10R")
      (footprint "eagle-import:0603")
      (libsource (lib "eagle-import") (part "R-0603"))
    )
    (comp (ref "R93")
      (value "300R")
      (footprint "eagle-import:0603")
      (libsource (lib "eagle-import") (part "R-0603"))
    )
    (comp (ref "R94")
      (value "180k")
      (footprint "eagle-import:0603")
      (libsource (lib "eagle-import") (part "R-0603"))
    )
    (comp (ref "R95")
      (value "4M99")
      (footprint "eagle-import:0603")
      (libsource (lib "eagle-import") (part "R-0603"))
    )
    (comp (ref "R96")
      (value "560k")
      (footprint "eagle-import:0603")
      (libsource (lib "eagle-import") (part "R-0603"))
    )
    (comp (ref "R97")
      (value "180k")
      (footprint "eagle-import:0603")
      (libsource (lib "eagle-import") (part "R-0603"))
    )
    (comp (ref "R98")
      (value "4M99")
      (footprint "eagle-import:0603")
      (libsource (lib "eagle-import") (part "R-0603"))
    )
    (comp (ref "R99")
      (value "560k")
      (footprint "eagle-import:0603")
      (libsource (lib "eagle-import") (part "R-0603"))
    )
    (comp (ref "R100")
      (value "2k2")
      (footprint "eagle-import:0603")
      (libsource (lib "eagle-import") (part "R-0603"))
    )
    (comp (ref "R101")
      (value "2k2")
      (footprint "eagle-import:0603")
      (libsource (lib "eagle-import") (part "R-0603"))
    )
    (comp (ref "R102")
      (value "1k")
      (footprint "eagle-import:0603")
      (libsource (lib "eagle-import") (part "R-0603"))
    )
    (comp (ref "R103")
      (value "300R")
      (footprint "eagle-import:0603")
      (libsource (lib "eagle-import") (part "R-0603"))
    )
    (comp (ref "R105")
      (value "1R")
      (footprint "eagle-import:0805")
      (libsource (lib "eagle-import") (part "R-0805"))
    )
    (comp (ref "R106")
      (value "1R")
      (footprint "eagle-import:0805")
      (libsource (lib "eagle-import") (part "R-0805"))
    )
    (comp (ref "R128")
      (value "10k")
      (footprint "eagle-import:0603")
      (libsource (lib "eagle-import") (part "R-0603"))
    )
    (comp (ref "R129")
      (value "DNP/0R")
      (footprint "eagle-import:0603")
      (libsource (lib "eagle-import") (part "R-0603"))
    )
    (comp (ref "R130")
      (value "100k")
      (footprint "eagle-import:0603")
      (libsource (lib "eagle-import") (part "R-0603"))
    )
    (comp (ref "R132")
      (value "1M")
      (footprint "eagle-import:0603")
      (libsource (lib "eagle-import") (part "R-0603"))
    )
    (comp (ref "REF1")
      (value "REF")
      (footprint "eagle-import:REF")
      (libsource (lib "eagle-import") (part "REF"))
    )
    (comp (ref "REF2")
      (value "REF")
      (footprint "eagle-import:REF")
      (libsource (lib "eagle-import") (part "REF"))
    )
    (comp (ref "T1")
      (value "PIC-OUT")
      (footprint "eagle-import:TEMP-PAD")
      (libsource (lib "eagle-import") (part "PIC-OUT"))
    )
    (comp (ref "T3")
      (value "PIC-RPX")
      (footprint "eagle-import:TEMP-PAD")
      (libsource (lib "eagle-import") (part "PIC-RPX"))
    )
    (comp (ref "T5")
      (value "PIC-OUT")
      (footprint "eagle-import:TEMP-PAD")
      (libsource (lib "eagle-import") (part "PIC-OUT"))
    )
    (comp (ref "T7")
      (value "PIC-OUT")
      (footprint "eagle-import:TEMP-PAD")
      (libsource (lib "eagle-import") (part "PIC-OUT"))
    )
    (comp (ref "T13")
      (value "PIC-RPX")
      (footprint "eagle-import:TEMP-PAD")
      (libsource (lib "eagle-import") (part "PIC-RPX"))
    )
    (comp (ref "T14")
      (value "PIC-RPX")
      (footprint "eagle-import:TEMP-PAD")
      (libsource (lib "eagle-import") (part "PIC-RPX"))
    )
    (comp (ref "T15")
      (value "PIC-OUT")
      (footprint "eagle-import:TEMP-PAD")
      (libsource (lib "eagle-import") (part "PIC-OUT"))
    )
    (comp (ref "T27")
      (value "PIC-OUT")
      (footprint "eagle-import:TEMP-PAD")
      (libsource (lib "eagle-import") (part "PIC-OUT"))
    )
    (comp (ref "T32")
      (value "PIC-OUT")
      (footprint "eagle-import:TEMP-PAD")
      (libsource (lib "eagle-import") (part "PIC-OUT"))
    )
    (comp (ref "T33")
      (value "PIC-OUT")
      (footprint "eagle-import:TEMP-PAD")
      (libsource (lib "eagle-import") (part "PIC-OUT"))
    )
    (comp (ref "T36")
      (value "PIC-OUT")
      (footprint "eagle-import:TEMP-PAD")
      (libsource (lib "eagle-import") (part "PIC-OUT"))
    )
    (comp (ref "T37")
      (value "PIN-AN")
      (footprint "eagle-import:TEMP-PAD")
      (libsource (lib "eagle-import") (part "PIN-AN"))
    )
    (comp (ref "T38")
      (value "PIN-AN")
      (footprint "eagle-import:TEMP-PAD")
      (libsource (lib "eagle-import") (part "PIN-AN"))
    )
    (comp (ref "T39")
      (value "PIN-AN")
      (footprint "eagle-import:TEMP-PAD")
      (libsource (lib "eagle-import") (part "PIN-AN"))
    )
    (comp (ref "T45")
      (value "PIC-RPX")
      (footprint "eagle-import:TEMP-PAD")
      (libsource (lib "eagle-import") (part "PIC-RPX"))
    )
    (comp (ref "TP1")
      (value "DNP-TestPoint")
      (footprint "eagle-import:SMD_ROUND_1MM")
      (libsource (lib "eagle-import") (part "ROUND_SMD1MM"))
    )
    (comp (ref "TP2")
      (value "DNP-TestPoint")
      (footprint "eagle-import:TH_ROUND_14MM08MM")
      (libsource (lib "eagle-import") (part "ROUND_SMDTH1.4MM"))
    )
    (comp (ref "TP4")
      (value "DNP-TestPoint")
      (footprint "eagle-import:TH_ROUND_14MM08MM")
      (libsource (lib "eagle-import") (part "ROUND_SMDTH1.4MM"))
    )
    (comp (ref "X1")
      (value "8MHz-5x3.2mm")
      (footprint "eagle-import:7B")
      (libsource (lib "eagle-import") (part "XTAL-7B"))
    )
  )
  (nets
    (net (code "1") (name "+3.3V") (class "Default")
      (node (ref "C47") (pin "1") (pinfunction "1_1") (pintype "passive"))
      (node (ref "C48") (pin "1") (pinfunction "1_1") (pintype "passive"))
      (node (ref "C49") (pin "1") (pinfunction "1_1") (pintype "passive"))
      (node (ref "C50") (pin "1") (pinfunction "1_1") (pintype "passive"))
      (node (ref "C51") (pin "1") (pinfunction "1_1") (pintype "passive"))
      (node (ref "C52") (pin "1") (pinfunction "1_1") (pintype "passive"))
      (node (ref "C69") (pin "1") (pinfunction "1_1") (pintype "passive"))
      (node (ref "C70") (pin "1") (pinfunction "1_1") (pintype "passive"))
      (node (ref "C81") (pin "+") (pinfunction "+_+") (pintype "passive"))
      (node (ref "IC1") (pin "16") (pinfunction "VDD3_16") (pintype "input"))
      (node (ref "IC1") (pin "2") (pinfunction "VDD2_2") (pintype "input"))
      (node (ref "IC1") (pin "37") (pinfunction "VDD4_37") (pintype "input"))
      (node (ref "IC1") (pin "46") (pinfunction "VDD5_46") (pintype "input"))
      (node (ref "IC1") (pin "55") (pinfunction "VUSB3V3_55") (pintype "input"))
      (node (ref "IC1") (pin "62") (pinfunction "VDD6_62") (pintype "input"))
      (node (ref "IC1") (pin "86") (pinfunction "VDD1_86") (pintype "input"))
      (node (ref "J17") (pin "2") (pinfunction "2_2") (pintype "passive"))
      (node (ref "L13") (pin "1") (pinfunction "1_1") (pintype "passive"))
      (node (ref "R103") (pin "2") (pinfunction "2_2") (pintype "passive"))
      (node (ref "R105") (pin "2") (pinfunction "2_2") (pintype "passive"))
      (node (ref "R106") (pin "2") (pinfunction "2_2") (pintype "passive"))
      (node (ref "R129") (pin "1") (pinfunction "1_1") (pintype "passive"))
      (node (ref "R28") (pin "2") (pinfunction "2_2") (pintype "passive"))
      (node (ref "R65") (pin "1") (pinfunction "1_1") (pintype "passive"))
      (node (ref "R82") (pin "1") (pinfunction "1_1") (pintype "passive"))
      (node (ref "R91") (pin "2") (pinfunction "2_2") (pintype "passive"))
    )
    (net (code "2") (name "+3.3V{slash}1") (class "Default")
      (node (ref "C27") (pin "1") (pinfunction "1_1") (pintype "passive"))
      (node (ref "C28") (pin "1") (pinfunction "1_1") (pintype "passive"))
      (node (ref "IC11") (pin "2") (pinfunction "A1_2") (pintype "input"))
      (node (ref "IC11") (pin "8") (pinfunction "VCC_8") (pintype "input"))
      (node (ref "IC7") (pin "8") (pinfunction "VCC_8") (pintype "input"))
      (node (ref "IC9") (pin "3") (pinfunction "/WP_3") (pintype "input"))
      (node (ref "IC9") (pin "7") (pinfunction "/HOLD_7") (pintype "input"))
      (node (ref "IC9") (pin "8") (pinfunction "VCC_8") (pintype "input"))
      (node (ref "Q2") (pin "3") (pinfunction "D_3") (pintype "passive"))
      (node (ref "Q2") (pin "P2") (pinfunction "D1_P2") (pintype "passive"))
      (node (ref "R18") (pin "1") (pinfunction "1_1") (pintype "passive"))
      (node (ref "R25") (pin "2") (pinfunction "2_2") (pintype "passive"))
      (node (ref "R26") (pin "1") (pinfunction "1_1") (pintype "passive"))
      (node (ref "R27") (pin "1") (pinfunction "1_1") (pintype "passive"))
    )
    (net (code "3") (name "+3.3V{slash}2") (class "Default")
      (node (ref "C41") (pin "1") (pinfunction "1_1") (pintype "passive"))
      (node (ref "C86") (pin "+") (pinfunction "+_+") (pintype "passive"))
      (node (ref "IC12") (pin "8") (pinfunction "VCC_8") (pintype "input"))
      (node (ref "Q1") (pin "3") (pinfunction "D_3") (pintype "passive"))
      (node (ref "Q1") (pin "P2") (pinfunction "D1_P2") (pintype "passive"))
      (node (ref "R30") (pin "2") (pinfunction "2_2") (pintype "passive"))
      (node (ref "R34") (pin "1") (pinfunction "1_1") (pintype "passive"))
      (node (ref "R72") (pin "1") (pinfunction "1_1") (pintype "passive"))
      (node (ref "R73") (pin "2") (pinfunction "2_2") (pintype "passive"))
    )
    (net (code "4") (name "/A+") (class "Default")
      (node (ref "IC14") (pin "3") (pinfunction "3_3") (pintype "passive"))
      (node (ref "J3") (pin "4") (pinfunction "4_4") (pintype "passive"))
      (node (ref "J4") (pin "4") (pinfunction "4_4") (pintype "passive"))
      (node (ref "L8") (pin "2") (pinfunction "2_2") (pintype "passive"))
    )
    (net (code "5") (name "/A++") (class "Default")
      (node (ref "IC12") (pin "6") (pinfunction "A_6") (pintype "bidirectional"))
      (node (ref "L8") (pin "1") (pinfunction "1_1") (pintype "passive"))
      (node (ref "R32") (pin "2") (pinfunction "2_2") (pintype "passive"))
      (node (ref "R34") (pin "2") (pinfunction "2_2") (pintype "passive"))
    )
    (net (code "6") (name "/ACT-L-SENSE") (class "Default")
      (node (ref "R1") (pin "7") (pinfunction "2_7") (pintype "passive"))
      (node (ref "R1") (pin "8") (pinfunction "2_8") (pintype "passive"))
    )
    (net (code "7") (name "/ACT-L-SW") (class "Default")
      (node (ref "C44") (pin "1") (pinfunction "1_1") (pintype "passive"))
      (node (ref "J14") (pin "2") (pinfunction "2_2") (pintype "passive"))
      (node (ref "R1") (pin "1") (pinfunction "1_1") (pintype "passive"))
      (node (ref "R2") (pin "8") (pinfunction "2_8") (pintype "passive"))
    )
    (net (code "8") (name "/ACT-R-SENSE") (class "Default")
      (node (ref "R1") (pin "5") (pinfunction "2_5") (pintype "passive"))
      (node (ref "R1") (pin "6") (pinfunction "2_6") (pintype "passive"))
    )
    (net (code "9") (name "/ACT-R-SW") (class "Default")
      (node (ref "C3") (pin "1") (pinfunction "1_1") (pintype "passive"))
      (node (ref "J15") (pin "2") (pinfunction "2_2") (pintype "passive"))
      (node (ref "R1") (pin "3") (pinfunction "1_3") (pintype "passive"))
      (node (ref "R2") (pin "7") (pinfunction "2_7") (pintype "passive"))
    )
    (net (code "10") (name "/ACT_EN") (class "Default")
      (node (ref "R11") (pin "5") (pinfunction "2_5") (pintype "passive"))
      (node (ref "R11") (pin "6") (pinfunction "2_6") (pintype "passive"))
      (node (ref "R7") (pin "4") (pinfunction "1_4") (pintype "passive"))
    )
    (net (code "11") (name "/ACT_L+") (class "Default")
      (node (ref "IC2") (pin "31") (pinfunction "OUT1A_31") (pintype "output"))
      (node (ref "J14") (pin "1") (pinfunction "1_1") (pintype "passive"))
    )
    (net (code "12") (name "/ACT_L-") (class "Default")
      (node (ref "IC2") (pin "23") (pinfunction "OUT2A_23") (pintype "output"))
      (node (ref "J14") (pin "3") (pinfunction "3_3") (pintype "passive"))
    )
    (net (code "13") (name "/ACT_L1") (class "Default")
      (node (ref "IC2") (pin "27") (pinfunction "IN1_A_27") (pintype "input"))
      (node (ref "R10") (pin "5") (pinfunction "2_5") (pintype "passive"))
    )
    (net (code "14") (name "/ACT_L2") (class "Default")
      (node (ref "IC2") (pin "28") (pinfunction "IN2_A_28") (pintype "input"))
      (node (ref "R10") (pin "6") (pinfunction "2_6") (pintype "passive"))
    )
    (net (code "15") (name "/ACT_R+") (class "Default")
      (node (ref "IC2") (pin "9") (pinfunction "OUT1B_9") (pintype "output"))
      (node (ref "J15") (pin "1") (pinfunction "1_1") (pintype "passive"))
    )
    (net (code "16") (name "/ACT_R-") (class "Default")
      (node (ref "IC2") (pin "19") (pinfunction "OUT2B_19") (pintype "output"))
      (node (ref "J15") (pin "3") (pinfunction "3_3") (pintype "passive"))
    )
    (net (code "17") (name "/ACT_R1") (class "Default")
      (node (ref "IC2") (pin "13") (pinfunction "IN1_B_13") (pintype "input"))
      (node (ref "R10") (pin "7") (pinfunction "2_7") (pintype "passive"))
    )
    (net (code "18") (name "/ACT_R2") (class "Default")
      (node (ref "IC2") (pin "14") (pinfunction "IN2_B_14") (pintype "input"))
      (node (ref "R10") (pin "8") (pinfunction "2_8") (pintype "passive"))
    )
    (net (code "19") (name "/B-") (class "Default")
      (node (ref "IC14") (pin "2") (pinfunction "2_2") (pintype "passive"))
      (node (ref "J3") (pin "5") (pinfunction "5_5") (pintype "passive"))
      (node (ref "J4") (pin "5") (pinfunction "5_5") (pintype "passive"))
      (node (ref "L7") (pin "2") (pinfunction "2_2") (pintype "passive"))
    )
    (net (code "20") (name "/B--") (class "Default")
      (node (ref "IC12") (pin "7") (pinfunction "B_7") (pintype "bidirectional"))
      (node (ref "L7") (pin "1") (pinfunction "1_1") (pintype "passive"))
      (node (ref "R31") (pin "1") (pinfunction "1_1") (pintype "passive"))
      (node (ref "R32") (pin "1") (pinfunction "1_1") (pintype "passive"))
    )
    (net (code "21") (name "/CURR-SENSE") (class "Default")
      (node (ref "C66") (pin "1") (pinfunction "1_1") (pintype "passive"))
      (node (ref "IC1") (pin "14") (pinfunction "AN19/C2INC/RPG9/PMA2/RG9_14") (pintype "bidirectional"))
      (node (ref "O8") (pin "P$1") (pinfunction "TP_P$1") (pintype "passive"))
      (node (ref "R102") (pin "2") (pinfunction "2_2") (pintype "passive"))
      (node (ref "T39") (pin "P$1") (pinfunction "TP_P$1") (pintype "passive"))
    )
    (net (code "22") (name "/D+") (class "Default")
      (node (ref "IC1") (pin "57") (pinfunction "D+/RG2_57") (pintype "bidirectional"))
      (node (ref "IC15") (pin "3") (pinfunction "3_3") (pintype "passive"))
      (node (ref "J12") (pin "3_D+") (pinfunction "D+_3_D+") (pintype "bidirectional"))
    )
    (net (code "23") (name "/D-") (class "Default")
      (node (ref "IC1") (pin "56") (pinfunction "D-/RG3_56") (pintype "bidirectional"))
      (node (ref "IC15") (pin "2") (pinfunction "2_2") (pintype "passive"))
      (node (ref "J12") (pin "2_D-") (pinfunction "D-_2_D-") (pintype "bidirectional"))
    )
    (net (code "24") (name "/DOOR_L") (class "Default")
      (node (ref "R50") (pin "2") (pinfunction "1_2") (pintype "passive"))
      (node (ref "R50") (pin "3") (pinfunction "1_3") (pintype "passive"))
    )
    (net (code "25") (name "/DOOR_L_SW") (class "Default")
      (node (ref "C12") (pin "1") (pinfunction "1_1") (pintype "passive"))
      (node (ref "J14") (pin "4") (pinfunction "4_4") (pintype "passive"))
      (node (ref "R50") (pin "7") (pinfunction "2_7") (pintype "passive"))
      (node (ref "R6") (pin "2") (pinfunction "2_2") (pintype "passive"))
    )
    (net (code "26") (name "/DOOR_ON") (class "Default")
      (node (ref "Q3") (pin "5") (pinfunction "Q1G_5") (pintype "input"))
      (node (ref "R9") (pin "7") (pinfunction "2_7") (pintype "passive"))
    )
    (net (code "27") (name "/DOOR_R") (class "Default")
      (node (ref "R50") (pin "1") (pinfunction "1_1") (pintype "passive"))
      (node (ref "R50") (pin "4") (pinfunction "1_4") (pintype "passive"))
    )
    (net (code "28") (name "/DOOR_R_SW") (class "Default")
      (node (ref "C4") (pin "1") (pinfunction "1_1") (pintype "passive"))
      (node (ref "J15") (pin "4") (pinfunction "4_4") (pintype "passive"))
      (node (ref "R50") (pin "8") (pinfunction "2_8") (pintype "passive"))
      (node (ref "R8") (pin "2") (pinfunction "2_2") (pintype "passive"))
    )
    (net (code "29") (name "/LAN-CTL") (class "Default")
      (node (ref "IC1") (pin "84") (pinfunction "PMD15/RD7_84") (pintype "bidirectional"))
      (node (ref "IC12") (pin "2") (pinfunction "/RE_2") (pintype "input"))
      (node (ref "IC12") (pin "3") (pinfunction "DE_3") (pintype "input"))
      (node (ref "O31") (pin "P$1") (pinfunction "TP_P$1") (pintype "passive"))
      (node (ref "R71") (pin "1") (pinfunction "1_1") (pintype "passive"))
      (node (ref "T15") (pin "P$1") (pinfunction "TP_P$1") (pintype "passive"))
    )
    (net (code "30") (name "/LAN-RX") (class "Default")
      (node (ref "IC1") (pin "88") (pinfunction "RPF1/PMD10/RF1_88") (pintype "bidirectional"))
      (node (ref "IC12") (pin "1") (pinfunction "R_1") (pintype "output"))
      (node (ref "O29") (pin "P$1") (pinfunction "TP_P$1") (pintype "passive"))
      (node (ref "R72") (pin "2") (pinfunction "2_2") (pintype "passive"))
      (node (ref "T13") (pin "P$1") (pinfunction "TP_P$1") (pintype "passive"))
    )
    (net (code "31") (name "/LAN-TX") (class "Default")
      (node (ref "IC1") (pin "87") (pinfunction "RPF0/PMD11/RF0_87") (pintype "bidirectional"))
      (node (ref "IC12") (pin "4") (pinfunction "D_4") (pintype "input"))
      (node (ref "O30") (pin "P$1") (pinfunction "TP_P$1") (pintype "passive"))
      (node (ref "R73") (pin "1") (pinfunction "1_1") (pintype "passive"))
      (node (ref "T14") (pin "P$1") (pinfunction "TP_P$1") (pintype "passive"))
    )
    (net (code "32") (name "/LED-PIC") (class "Default")
      (node (ref "IC1") (pin "1") (pinfunction "RG15_1") (pintype "bidirectional"))
      (node (ref "O1") (pin "P$1") (pinfunction "TP_P$1") (pintype "passive"))
      (node (ref "R29") (pin "1") (pinfunction "1_1") (pintype "passive"))
      (node (ref "T36") (pin "P$1") (pinfunction "TP_P$1") (pintype "passive"))
      (node (ref "TP4") (pin "P$1") (pinfunction "TP_P$1") (pintype "passive"))
    )
    (net (code "33") (name "/PGC") (class "Default")
      (node (ref "IC1") (pin "24") (pinfunction "PGEC1/AN1/RPB1/CTED12/RB1_24") (pintype "bidirectional"))
      (node (ref "J17") (pin "5") (pinfunction "5_5") (pintype "passive"))
    )
    (net (code "34") (name "/PGD") (class "Default")
      (node (ref "IC1") (pin "25") (pinfunction "PGED1/AN0/RPB0/RB0_25") (pintype "bidirectional"))
      (node (ref "J17") (pin "4") (pinfunction "4_4") (pintype "passive"))
      (node (ref "R130") (pin "2") (pinfunction "2_2") (pintype "passive"))
    )
    (net (code "35") (name "/POWER-GOOD") (class "Default")
      (node (ref "IC6") (pin "4") (pinfunction "OUT_4") (pintype "output"))
      (node (ref "R130") (pin "1") (pinfunction "1_1") (pintype "passive"))
      (node (ref "T45") (pin "P$1") (pinfunction "TP_P$1") (pintype "passive"))
      (node (ref "TP2") (pin "P$1") (pinfunction "TP_P$1") (pintype "passive"))
    )
    (net (code "36") (name "/REF-EN") (class "Default")
      (node (ref "IC1") (pin "28") (pinfunction "VREF-/CVREF-/PMA7/RA9_28") (pintype "bidirectional"))
      (node (ref "R93") (pin "1") (pinfunction "1_1") (pintype "passive"))
    )
    (net (code "37") (name "/REF2,5V") (class "Default")
      (node (ref "C57") (pin "1") (pinfunction "1_1") (pintype "passive"))
      (node (ref "IC1") (pin "29") (pinfunction "VREF+/CVREF+/PMA6/RA10_29") (pintype "bidirectional"))
      (node (ref "IC13") (pin "2") (pinfunction "VOUT_2") (pintype "bidirectional"))
    )
    (net (code "38") (name "/SCL1-EEPROM") (class "Default")
      (node (ref "IC1") (pin "66") (pinfunction "SCL1/RPA14/RA14_66") (pintype "bidirectional"))
      (node (ref "IC11") (pin "6") (pinfunction "SCL_6") (pintype "input"))
      (node (ref "IC7") (pin "6") (pinfunction "SCL_6") (pintype "input"))
      (node (ref "R26") (pin "2") (pinfunction "2_2") (pintype "passive"))
    )
    (net (code "39") (name "/SCLK2-SPI") (class "Default")
      (node (ref "IC1") (pin "10") (pinfunction "AN16/C1IND/RPG6/SCK2/PMA5/RG6_10") (pintype "bidirectional"))
      (node (ref "IC9") (pin "6") (pinfunction "C_6") (pintype "input"))
    )
    (net (code "40") (name "/SD-CS") (class "Default")
      (node (ref "IC1") (pin "9") (pinfunction "RPC4/CTED7/RC4_9") (pintype "bidirectional"))
      (node (ref "O5") (pin "P$1") (pinfunction "TP_P$1") (pintype "passive"))
    )
    (net (code "41") (name "/SDA1-EEPROM") (class "Default")
      (node (ref "IC1") (pin "67") (pinfunction "SDA1/RPA15/RA15_67") (pintype "bidirectional"))
      (node (ref "IC11") (pin "5") (pinfunction "SDA_5") (pintype "bidirectional"))
      (node (ref "IC7") (pin "5") (pinfunction "SDA_5") (pintype "bidirectional"))
      (node (ref "R27") (pin "2") (pinfunction "2_2") (pintype "passive"))
    )
    (net (code "42") (name "/SDI2-MISO") (class "Default")
      (node (ref "IC1") (pin "22") (pinfunction "PGED3/AN3/C2INA/RPB3/RB3_22") (pintype "bidirectional"))
      (node (ref "IC9") (pin "2") (pinfunction "Q_2") (pintype "bidirectional"))
      (node (ref "O13") (pin "P$1") (pinfunction "TP_P$1") (pintype "passive"))
    )
    (net (code "43") (name "/SDO2-MOSI") (class "Default")
      (node (ref "IC1") (pin "20") (pinfunction "AN5/C1INA/RPB5/RB5_20") (pintype "bidirectional"))
      (node (ref "IC9") (pin "5") (pinfunction "D_5") (pintype "input"))
      (node (ref "O12") (pin "P$1") (pinfunction "TP_P$1") (pintype "passive"))
    )
    (net (code "44") (name "/VACT-ON") (class "Default")
      (node (ref "Q6") (pin "2") (pinfunction "G_2") (pintype "passive"))
      (node (ref "R12") (pin "1") (pinfunction "1_1") (pintype "passive"))
      (node (ref "T1") (pin "P$1") (pinfunction "TP_P$1") (pintype "passive"))
    )
    (net (code "45") (name "/VBAT-LAN") (class "Default")
      (node (ref "D3") (pin "C") (pinfunction "C_C") (pintype "passive"))
      (node (ref "J3") (pin "1") (pinfunction "1_1") (pintype "passive"))
      (node (ref "J3") (pin "3") (pinfunction "3_3") (pintype "passive"))
      (node (ref "J4") (pin "1") (pinfunction "1_1") (pintype "passive"))
      (node (ref "J4") (pin "3") (pinfunction "3_3") (pintype "passive"))
      (node (ref "L11") (pin "2") (pinfunction "2_2") (pintype "passive"))
    )
    (net (code "46") (name "/VBAT-LAN-F") (class "Default")
      (node (ref "C33") (pin "1") (pinfunction "1_1") (pintype "passive"))
      (node (ref "C34") (pin "1") (pinfunction "1_1") (pintype "passive"))
      (node (ref "D6") (pin "K") (pinfunction "K_K") (pintype "passive"))
      (node (ref "L11") (pin "1") (pinfunction "1_1") (pintype "passive"))
      (node (ref "Q5") (pin "2") (pinfunction "S_2") (pintype "passive"))
      (node (ref "Q5") (pin "5") (pinfunction "S_5") (pintype "passive"))
      (node (ref "R132") (pin "1") (pinfunction "1_1") (pintype "passive"))
      (node (ref "R36") (pin "2") (pinfunction "2_2") (pintype "passive"))
      (node (ref "R38") (pin "2") (pinfunction "2_2") (pintype "passive"))
      (node (ref "R42") (pin "1") (pinfunction "1_1") (pintype "passive"))
      (node (ref "R45") (pin "1") (pinfunction "1_1") (pintype "passive"))
      (node (ref "R94") (pin "1") (pinfunction "1_1") (pintype "passive"))
    )
    (net (code "47") (name "/VBAT-ON") (class "Default")
      (node (ref "IC1") (pin "52") (pinfunction "RPF2/RF2_52") (pintype "bidirectional"))
      (node (ref "O42") (pin "P$1") (pinfunction "TP_P$1") (pintype "passive"))
      (node (ref "Q4") (pin "2") (pinfunction "G_2") (pintype "passive"))
      (node (ref "R132") (pin "2") (pinfunction "2_2") (pintype "passive"))
      (node (ref "R41") (pin "1") (pinfunction "1_1") (pintype "passive"))
      (node (ref "T5") (pin "P$1") (pinfunction "TP_P$1") (pintype "passive"))
    )
    (net (code "48") (name "/VBAT-SENSE") (class "Default")
      (node (ref "C64") (pin "1") (pinfunction "1_1") (pintype "passive"))
      (node (ref "IC1") (pin "26") (pinfunction "PGEC2/AN6/RPB6/RB6_26") (pintype "bidirectional"))
      (node (ref "O15") (pin "P$1") (pinfunction "TP_P$1") (pintype "passive"))
      (node (ref "R100") (pin "1") (pinfunction "1_1") (pintype "passive"))
      (node (ref "T37") (pin "P$1") (pinfunction "TP_P$1") (pintype "passive"))
    )
    (net (code "49") (name "/VBATLAN-SENSE") (class "Default")
      (node (ref "C36") (pin "1") (pinfunction "1_1") (pintype "passive"))
      (node (ref "IC1") (pin "27") (pinfunction "PGED2/AN7/RPB7/CTED3/RB7_27") (pintype "bidirectional"))
      (node (ref "O16") (pin "P$1") (pinfunction "TP_P$1") (pintype "passive"))
      (node (ref "R101") (pin "1") (pinfunction "1_1") (pintype "passive"))
      (node (ref "T38") (pin "P$1") (pinfunction "TP_P$1") (pintype "passive"))
    )
    (net (code "50") (name "/VBUS") (class "Default")
      (node (ref "IC1") (pin "54") (pinfunction "VBUS_54") (pintype "input"))
      (node (ref "R128") (pin "2") (pinfunction "2_2") (pintype "passive"))
    )
    (net (code "51") (name "/VPS-ON") (class "Default")
      (node (ref "IC1") (pin "53") (pinfunction "RPF8/RF8_53") (pintype "bidirectional"))
      (node (ref "O41") (pin "P$1") (pinfunction "TP_P$1") (pintype "passive"))
      (node (ref "Q4") (pin "5") (pinfunction "G_5") (pintype "passive"))
      (node (ref "R44") (pin "1") (pinfunction "1_1") (pintype "passive"))
      (node (ref "T7") (pin "P$1") (pinfunction "TP_P$1") (pintype "passive"))
    )
    (net (code "52") (name "/VPS-PWR") (class "Default")
      (node (ref "D4") (pin "C") (pinfunction "C_C") (pintype "passive"))
      (node (ref "J3") (pin "6") (pinfunction "6_6") (pintype "passive"))
      (node (ref "J4") (pin "6") (pinfunction "6_6") (pintype "passive"))
      (node (ref "L10") (pin "2") (pinfunction "2_2") (pintype "passive"))
    )
    (net (code "53") (name "/VPS-PWR-F") (class "Default")
      (node (ref "L10") (pin "1") (pinfunction "1_1") (pintype "passive"))
      (node (ref "Q5") (pin "4") (pinfunction "D_4") (pintype "passive"))
      (node (ref "R23") (pin "2") (pinfunction "2_2") (pintype "passive"))
    )
    (net (code "54") (name "/VPS-SENSE") (class "Default")
      (node (ref "C65") (pin "1") (pinfunction "1_1") (pintype "passive"))
      (node (ref "IC1") (pin "12") (pinfunction "AN18/C2IND/RPG8/PMA3/RG8_12") (pintype "bidirectional"))
      (node (ref "O7") (pin "P$1") (pinfunction "TP_P$1") (pintype "passive"))
      (node (ref "R48") (pin "2") (pinfunction "2_2") (pintype "passive"))
      (node (ref "R49") (pin "1") (pinfunction "1_1") (pintype "passive"))
      (node (ref "T3") (pin "P$1") (pinfunction "TP_P$1") (pintype "passive"))
    )
    (net (code "55") (name "/{slash}3.3V1PWRON") (class "Default")
      (node (ref "IC1") (pin "21") (pinfunction "AN4/C1INB/USBOEN/RB4_21") (pintype "bidirectional"))
      (node (ref "O44") (pin "P$1") (pinfunction "TP_P$1") (pintype "passive"))
      (node (ref "R24") (pin "2") (pinfunction "2_2") (pintype "passive"))
      (node (ref "T32") (pin "P$1") (pinfunction "TP_P$1") (pintype "passive"))
    )
    (net (code "56") (name "/{slash}3.3V2PWRON") (class "Default")
      (node (ref "IC1") (pin "96") (pinfunction "TRD1/RG12_96") (pintype "bidirectional"))
      (node (ref "O23") (pin "P$1") (pinfunction "TP_P$1") (pintype "passive"))
      (node (ref "R75") (pin "2") (pinfunction "2_2") (pintype "passive"))
      (node (ref "T33") (pin "P$1") (pinfunction "TP_P$1") (pintype "passive"))
    )
    (net (code "57") (name "/{slash}FMEM1-CS") (class "Default")
      (node (ref "IC1") (pin "11") (pinfunction "AN17/C1INC/RPG7/PMA4/RG7_11") (pintype "bidirectional"))
      (node (ref "IC9") (pin "1") (pinfunction "/S_1") (pintype "input"))
      (node (ref "O6") (pin "P$1") (pinfunction "TP_P$1") (pintype "passive"))
      (node (ref "R25") (pin "1") (pinfunction "1_1") (pintype "passive"))
      (node (ref "T27") (pin "P$1") (pinfunction "TP_P$1") (pintype "passive"))
    )
    (net (code "58") (name "/{slash}MCLR") (class "Default")
      (node (ref "IC1") (pin "13") (pinfunction "~{MCLR}_13") (pintype "input"))
      (node (ref "J17") (pin "1") (pinfunction "1_1") (pintype "passive"))
      (node (ref "R90") (pin "2") (pinfunction "2_2") (pintype "passive"))
    )
    (net (code "59") (name "DGND") (class "Default")
      (node (ref "C22") (pin "2") (pinfunction "2_2") (pintype "passive"))
      (node (ref "C23") (pin "2") (pinfunction "2_2") (pintype "passive"))
      (node (ref "C24") (pin "1") (pinfunction "1_1") (pintype "passive"))
      (node (ref "C27") (pin "2") (pinfunction "2_2") (pintype "passive"))
      (node (ref "C28") (pin "2") (pinfunction "2_2") (pintype "passive"))
      (node (ref "C29") (pin "2") (pinfunction "2_2") (pintype "passive"))
      (node (ref "C30") (pin "2") (pinfunction "2_2") (pintype "passive"))
      (node (ref "C31") (pin "-") (pinfunction "-_-") (pintype "passive"))
      (node (ref "C35") (pin "2") (pinfunction "2_2") (pintype "passive"))
      (node (ref "C36") (pin "2") (pinfunction "2_2") (pintype "passive"))
      (node (ref "C40") (pin "2") (pinfunction "2_2") (pintype "passive"))
      (node (ref "C41") (pin "2") (pinfunction "2_2") (pintype "passive"))
      (node (ref "C47") (pin "2") (pinfunction "2_2") (pintype "passive"))
      (node (ref "C48") (pin "2") (pinfunction "2_2") (pintype "passive"))
      (node (ref "C49") (pin "2") (pinfunction "2_2") (pintype "passive"))
      (node (ref "C50") (pin "2") (pinfunction "2_2") (pintype "passive"))
      (node (ref "C51") (pin "2") (pinfunction "2_2") (pintype "passive"))
      (node (ref "C52") (pin "2") (pinfunction "2_2") (pintype "passive"))
      (node (ref "C53") (pin "2") (pinfunction "2_2") (pintype "passive"))
      (node (ref "C54") (pin "-") (pinfunction "-_-") (pintype "passive"))
      (node (ref "C55") (pin "2") (pinfunction "2_2") (pintype "passive"))
      (node (ref "C56") (pin "-") (pinfunction "-_-") (pintype "passive"))
      (node (ref "C57") (pin "2") (pinfunction "2_2") (pintype "passive"))
      (node (ref "C58") (pin "2") (pinfunction "2_2") (pintype "passive"))
      (node (ref "C59") (pin "2") (pinfunction "2_2") (pintype "passive"))
      (node (ref "C60") (pin "2") (pinfunction "2_2") (pintype "passive"))
      (node (ref "C61") (pin "2") (pinfunction "2_2") (pintype "passive"))
      (node (ref "C62") (pin "2") (pinfunction "2_2") (pintype "passive"))
      (node (ref "C63") (pin "2") (pinfunction "2_2") (pintype "passive"))
      (node (ref "C64") (pin "2") (pinfunction "2_2") (pintype "passive"))
      (node (ref "C65") (pin "2") (pinfunction "2_2") (pintype "passive"))
      (node (ref "C66") (pin "2") (pinfunction "2_2") (pintype "passive"))
      (node (ref "C67") (pin "2") (pinfunction "2_2") (pintype "passive"))
      (node (ref "C81") (pin "-") (pinfunction "-_-") (pintype "passive"))
      (node (ref "C83") (pin "2") (pinfunction "2_2") (pintype "passive"))
      (node (ref "C84") (pin "2") (pinfunction "2_2") (pintype "passive"))
      (node (ref "C85") (pin "2") (pinfunction "2_2") (pintype "passive"))
      (node (ref "C86") (pin "-") (pinfunction "-_-") (pintype "passive"))
      (node (ref "C88") (pin "2") (pinfunction "2_2") (pintype "passive"))
      (node (ref "D2") (pin "-") (pinfunction "A_-") (pintype "passive"))
      (node (ref "D5") (pin "K") (pinfunction "K_K") (pintype "passive"))
      (node (ref "D7") (pin "A") (pinfunction "A_A") (pintype "passive"))
      (node (ref "IC1") (pin "15") (pinfunction "VSS2_15") (pintype "input"))
      (node (ref "IC1") (pin "31") (pinfunction "AVSS_31") (pintype "input"))
      (node (ref "IC1") (pin "36") (pinfunction "VSS3_36") (pintype "input"))
      (node (ref "IC1") (pin "45") (pinfunction "VSS4_45") (pintype "input"))
      (node (ref "IC1") (pin "65") (pinfunction "VSS5_65") (pintype "input"))
      (node (ref "IC1") (pin "75") (pinfunction "VSS1_75") (pintype "input"))
      (node (ref "IC10") (pin "1") (pinfunction "GND_1") (pintype "input"))
      (node (ref "IC10") (pin "2") (pinfunction "GND1_2") (pintype "input"))
      (node (ref "IC11") (pin "1") (pinfunction "A0_1") (pintype "input"))
      (node (ref "IC11") (pin "3") (pinfunction "A2_3") (pintype "input"))
      (node (ref "IC11") (pin "4") (pinfunction "GND_4") (pintype "input"))
      (node (ref "IC12") (pin "5") (pinfunction "GND_5") (pintype "input"))
      (node (ref "IC13") (pin "3") (pinfunction "GND_3") (pintype "bidirectional"))
      (node (ref "IC15") (pin "1") (pinfunction "1_1") (pintype "input"))
      (node (ref "IC16") (pin "4") (pinfunction "V-_4") (pintype "input"))
      (node (ref "IC3") (pin "10") (pinfunction "SYNC_10") (pintype "input"))
      (node (ref "IC3") (pin "EP") (pinfunction "GND_EP") (pintype "input"))
      (node (ref "IC6") (pin "2") (pinfunction "GND_2") (pintype "input"))
      (node (ref "IC7") (pin "1") (pinfunction "A0_1") (pintype "input"))
      (node (ref "IC7") (pin "2") (pinfunction "A1_2") (pintype "input"))
      (node (ref "IC7") (pin "3") (pinfunction "A2_3") (pintype "input"))
      (node (ref "IC7") (pin "4") (pinfunction "GND_4") (pintype "input"))
      (node (ref "IC7") (pin "7") (pinfunction "WP_7") (pintype "input"))
      (node (ref "IC9") (pin "4") (pinfunction "GND_4") (pintype "input"))
      (node (ref "J12") (pin "4_GND") (pinfunction "GND_4_GND") (pintype "bidirectional"))
      (node (ref "J12") (pin "SH1") (pinfunction "GND_SH1_SH1") (pintype "bidirectional"))
      (node (ref "J12") (pin "SH2") (pinfunction "GND_SH2_SH2") (pintype "bidirectional"))
      (node (ref "J17") (pin "3") (pinfunction "3_3") (pintype "passive"))
      (node (ref "L12") (pin "1") (pinfunction "1_1") (pintype "passive"))
      (node (ref "L2") (pin "2") (pinfunction "2_2") (pintype "passive"))
      (node (ref "R12") (pin "2") (pinfunction "2_2") (pintype "passive"))
      (node (ref "R14") (pin "1") (pinfunction "1_1") (pintype "passive"))
      (node (ref "R17") (pin "2") (pinfunction "2_2") (pintype "passive"))
      (node (ref "R19") (pin "2") (pinfunction "2_2") (pintype "passive"))
      (node (ref "R21") (pin "2") (pinfunction "2_2") (pintype "passive"))
      (node (ref "R31") (pin "2") (pinfunction "2_2") (pintype "passive"))
      (node (ref "R40") (pin "1") (pinfunction "1_1") (pintype "passive"))
      (node (ref "R41") (pin "2") (pinfunction "2_2") (pintype "passive"))
      (node (ref "R43") (pin "1") (pinfunction "1_1") (pintype "passive"))
      (node (ref "R44") (pin "2") (pinfunction "2_2") (pintype "passive"))
      (node (ref "R46") (pin "1") (pinfunction "1_1") (pintype "passive"))
      (node (ref "R48") (pin "1") (pinfunction "1_1") (pintype "passive"))
      (node (ref "R71") (pin "2") (pinfunction "2_2") (pintype "passive"))
      (node (ref "R96") (pin "2") (pinfunction "2_2") (pintype "passive"))
      (node (ref "R99") (pin "2") (pinfunction "2_2") (pintype "passive"))
    )
    (net (code "60") (name "Net-(C24-Pad2)") (class "Default")
      (node (ref "C24") (pin "2") (pinfunction "2_2") (pintype "passive"))
      (node (ref "R77") (pin "2") (pinfunction "2_2") (pintype "passive"))
    )
    (net (code "61") (name "Net-(C39-Pad1)") (class "Default")
      (node (ref "C39") (pin "1") (pinfunction "1_1") (pintype "passive"))
      (node (ref "IC14") (pin "4") (pinfunction "4_4") (pintype "input"))
      (node (ref "R30") (pin "1") (pinfunction "1_1") (pintype "passive"))
    )
    (net (code "62") (name "Net-(C39-Pad2)") (class "Default")
      (node (ref "C39") (pin "2") (pinfunction "2_2") (pintype "passive"))
      (node (ref "D3") (pin "A") (pinfunction "A_A") (pintype "passive"))
      (node (ref "D4") (pin "A") (pinfunction "A_A") (pintype "passive"))
      (node (ref "IC14") (pin "1") (pinfunction "1_1") (pintype "input"))
      (node (ref "J3") (pin "2") (pinfunction "2_2") (pintype "passive"))
      (node (ref "J3") (pin "7") (pinfunction "7_7") (pintype "passive"))
      (node (ref "J3") (pin "8") (pinfunction "8_8") (pintype "passive"))
      (node (ref "J4") (pin "2") (pinfunction "2_2") (pintype "passive"))
      (node (ref "J4") (pin "7") (pinfunction "7_7") (pintype "passive"))
      (node (ref "J4") (pin "8") (pinfunction "8_8") (pintype "passive"))
      (node (ref "L12") (pin "2") (pinfunction "2_2") (pintype "passive"))
    )
    (net (code "63") (name "Net-(C40-Pad1)") (class "Default")
      (node (ref "C40") (pin "1") (pinfunction "1_1") (pintype "passive"))
      (node (ref "R90") (pin "1") (pinfunction "1_1") (pintype "passive"))
      (node (ref "R91") (pin "1") (pinfunction "1_1") (pintype "passive"))
    )
    (net (code "64") (name "Net-(D1-K)") (class "Default")
      (node (ref "C37") (pin "2") (pinfunction "2_2") (pintype "passive"))
      (node (ref "D1") (pin "2") (pinfunction "K_2") (pintype "passive"))
      (node (ref "IC2") (pin "17") (pinfunction "VBOOT_17") (pintype "input"))
    )
    (net (code "65") (name "Net-(D1-KA)") (class "Default")
      (node (ref "C2") (pin "1") (pinfunction "1_1") (pintype "passive"))
      (node (ref "D1") (pin "3") (pinfunction "KA_3") (pintype "passive"))
    )
    (net (code "66") (name "Net-(D2-C)") (class "Default")
      (node (ref "C26") (pin "1") (pinfunction "1_1") (pintype "passive"))
      (node (ref "C30") (pin "1") (pinfunction "1_1") (pintype "passive"))
      (node (ref "C31") (pin "+") (pinfunction "+_+") (pintype "passive"))
      (node (ref "D2") (pin "+") (pinfunction "C_+") (pintype "passive"))
      (node (ref "IC3") (pin "1") (pinfunction "BD_1") (pintype "input"))
      (node (ref "L9") (pin "2") (pinfunction "2_2") (pintype "passive"))
      (node (ref "R129") (pin "2") (pinfunction "2_2") (pintype "passive"))
      (node (ref "R20") (pin "1") (pinfunction "1_1") (pintype "passive"))
    )
    (net (code "67") (name "Net-(D5-PadA)") (class "Default")
      (node (ref "D5") (pin "A") (pinfunction "A_A") (pintype "passive"))
      (node (ref "R29") (pin "2") (pinfunction "2_2") (pintype "passive"))
    )
    (net (code "68") (name "Net-(D9-C)") (class "Default")
      (node (ref "D9") (pin "3") (pinfunction "C_3") (pintype "passive"))
      (node (ref "R2") (pin "1") (pinfunction "1_1") (pintype "passive"))
      (node (ref "R2") (pin "2") (pinfunction "1_2") (pintype "passive"))
      (node (ref "R7") (pin "6") (pinfunction "2_6") (pintype "passive"))
    )
    (net (code "69") (name "Net-(IC1-AVDD)") (class "Default")
      (node (ref "C55") (pin "1") (pinfunction "1_1") (pintype "passive"))
      (node (ref "C56") (pin "+") (pinfunction "+_+") (pintype "passive"))
      (node (ref "C88") (pin "1") (pinfunction "1_1") (pintype "passive"))
      (node (ref "IC1") (pin "30") (pinfunction "AVDD_30") (pintype "input"))
      (node (ref "R92") (pin "2") (pinfunction "2_2") (pintype "passive"))
    )
    (net (code "70") (name "Net-(IC1-CLKI{slash}RC12{slash}OSC1)") (class "Default")
      (node (ref "C60") (pin "1") (pinfunction "1_1") (pintype "passive"))
      (node (ref "IC1") (pin "63") (pinfunction "CLKI/RC12/OSC1_63") (pintype "bidirectional"))
      (node (ref "X1") (pin "3") (pinfunction "2_3") (pintype "passive"))
    )
    (net (code "71") (name "Net-(IC1-CLKO{slash}RC15{slash}OSC2)") (class "Default")
      (node (ref "C61") (pin "1") (pinfunction "1_1") (pintype "passive"))
      (node (ref "IC1") (pin "64") (pinfunction "CLKO/RC15/OSC2_64") (pintype "bidirectional"))
      (node (ref "X1") (pin "1") (pinfunction "1_1") (pintype "passive"))
    )
    (net (code "72") (name "Net-(IC1-VCAP)") (class "Default")
      (node (ref "C53") (pin "1") (pinfunction "1_1") (pintype "passive"))
      (node (ref "C54") (pin "+") (pinfunction "+_+") (pintype "passive"))
      (node (ref "IC1") (pin "85") (pinfunction "VCAP_85") (pintype "input"))
    )
    (net (code "73") (name "Net-(IC2-EN_A)") (class "Default")
      (node (ref "C5") (pin "1") (pinfunction "1_1") (pintype "passive"))
      (node (ref "IC2") (pin "25") (pinfunction "EN_A_25") (pintype "input"))
      (node (ref "R11") (pin "4") (pinfunction "1_4") (pintype "passive"))
    )
    (net (code "74") (name "Net-(IC2-EN_B)") (class "Default")
      (node (ref "C43") (pin "1") (pinfunction "1_1") (pintype "passive"))
      (node (ref "IC2") (pin "16") (pinfunction "EN_B_16") (pintype "input"))
      (node (ref "R11") (pin "3") (pinfunction "1_3") (pintype "passive"))
    )
    (net (code "75") (name "Net-(IC2-RCA)") (class "Default")
      (node (ref "C7") (pin "1") (pinfunction "1_1") (pintype "passive"))
      (node (ref "IC2") (pin "30") (pinfunction "RCA_30") (pintype "input"))
      (node (ref "R11") (pin "2") (pinfunction "1_2") (pintype "passive"))
    )
    (net (code "76") (name "Net-(IC2-RCB)") (class "Default")
      (node (ref "C6") (pin "1") (pinfunction "1_1") (pintype "passive"))
      (node (ref "IC2") (pin "11") (pinfunction "RCB_11") (pintype "input"))
      (node (ref "R11") (pin "1") (pinfunction "1_1") (pintype "passive"))
    )
    (net (code "77") (name "Net-(IC2-SENSE_A)") (class "Default")
      (node (ref "IC2") (pin "29") (pinfunction "SENSE_A_29") (pintype "input"))
      (node (ref "R5") (pin "2") (pinfunction "2_2") (pintype "passive"))
    )
    (net (code "78") (name "Net-(IC2-SENSE_B)") (class "Default")
      (node (ref "IC2") (pin "12") (pinfunction "SENSE_B_12") (pintype "input"))
      (node (ref "R4") (pin "2") (pinfunction "2_2") (pintype "passive"))
    )
    (net (code "79") (name "Net-(IC2-VCP)") (class "Default")
      (node (ref "C2") (pin "2") (pinfunction "2_2") (pintype "passive"))
      (node (ref "IC2") (pin "24") (pinfunction "VCP_24") (pintype "input"))
    )
    (net (code "80") (name "Net-(IC2-VREF_A)") (class "Default")
      (node (ref "IC2") (pin "15") (pinfunction "VREF_B_15") (pintype "input"))
      (node (ref "IC2") (pin "26") (pinfunction "VREF_A_26") (pintype "input"))
      (node (ref "R3") (pin "2") (pinfunction "2_2") (pintype "passive"))
      (node (ref "R7") (pin "5") (pinfunction "2_5") (pintype "passive"))
    )
    (net (code "81") (name "Net-(IC3-BOOST)") (class "Default")
      (node (ref "C25") (pin "2") (pinfunction "2_2") (pintype "passive"))
      (node (ref "IC3") (pin "2") (pinfunction "BOOST_2") (pintype "input"))
    )
    (net (code "82") (name "Net-(IC3-EN)") (class "Default")
      (node (ref "IC3") (pin "5") (pinfunction "EN_5") (pintype "input"))
      (node (ref "JP1") (pin "2") (pinfunction "2_2") (pintype "bidirectional"))
      (node (ref "R22") (pin "2") (pinfunction "2_2") (pintype "passive"))
    )
    (net (code "83") (name "Net-(IC3-FB)") (class "Default")
      (node (ref "C26") (pin "2") (pinfunction "2_2") (pintype "passive"))
      (node (ref "IC3") (pin "6") (pinfunction "FB_6") (pintype "input"))
      (node (ref "R19") (pin "1") (pinfunction "1_1") (pintype "passive"))
      (node (ref "R20") (pin "2") (pinfunction "2_2") (pintype "passive"))
    )
    (net (code "84") (name "Net-(IC3-RT)") (class "Default")
      (node (ref "IC3") (pin "8") (pinfunction "RT_8") (pintype "input"))
      (node (ref "R17") (pin "1") (pinfunction "1_1") (pintype "passive"))
    )
    (net (code "85") (name "Net-(IC3-SS)") (class "Default")
      (node (ref "IC3") (pin "7") (pinfunction "SS_7") (pintype "input"))
      (node (ref "R77") (pin "1") (pinfunction "1_1") (pintype "passive"))
    )
    (net (code "86") (name "Net-(IC3-SW)") (class "Default")
      (node (ref "C25") (pin "1") (pinfunction "1_1") (pintype "passive"))
      (node (ref "D7") (pin "K") (pinfunction "K_K") (pintype "passive"))
      (node (ref "IC3") (pin "3") (pinfunction "SW_3") (pintype "output"))
      (node (ref "L9") (pin "1") (pinfunction "1_1") (pintype "passive"))
    )
    (net (code "87") (name "Net-(IC6-HTH)") (class "Default")
      (node (ref "IC6") (pin "1") (pinfunction "HTH_1") (pintype "input"))
      (node (ref "R46") (pin "2") (pinfunction "2_2") (pintype "passive"))
      (node (ref "R47") (pin "1") (pinfunction "1_1") (pintype "passive"))
    )
    (net (code "88") (name "Net-(IC6-LTH)") (class "Default")
      (node (ref "IC6") (pin "3") (pinfunction "LTH_3") (pintype "input"))
      (node (ref "R33") (pin "1") (pinfunction "1_1") (pintype "passive"))
      (node (ref "R47") (pin "2") (pinfunction "2_2") (pintype "passive"))
    )
    (net (code "89") (name "Net-(IC6-VDD)") (class "Default")
      (node (ref "C35") (pin "1") (pinfunction "1_1") (pintype "passive"))
      (node (ref "IC6") (pin "5") (pinfunction "VDD_5") (pintype "input"))
      (node (ref "R28") (pin "1") (pinfunction "1_1") (pintype "passive"))
    )
    (net (code "90") (name "Net-(IC10-OUT)") (class "Default")
      (node (ref "IC10") (pin "3") (pinfunction "OUT_3") (pintype "output"))
      (node (ref "R102") (pin "1") (pinfunction "1_1") (pintype "passive"))
    )
    (net (code "91") (name "Net-(IC10-VIN+)") (class "Default")
      (node (ref "C29") (pin "1") (pinfunction "1_1") (pintype "passive"))
      (node (ref "F1") (pin "1") (pinfunction "1_1") (pintype "passive"))
      (node (ref "IC10") (pin "5") (pinfunction "VIN+_5") (pintype "input"))
      (node (ref "R39") (pin "2") (pinfunction "2_2") (pintype "passive"))
    )
    (net (code "92") (name "Net-(IC11-WP)") (class "Default")
      (node (ref "IC11") (pin "7") (pinfunction "WP_7") (pintype "input"))
      (node (ref "R18") (pin "2") (pinfunction "2_2") (pintype "passive"))
      (node (ref "TP1") (pin "P$1") (pinfunction "TP_P$1") (pintype "passive"))
    )
    (net (code "93") (name "Net-(IC13-VIN)") (class "Default")
      (node (ref "C58") (pin "1") (pinfunction "1_1") (pintype "passive"))
      (node (ref "C59") (pin "1") (pinfunction "1_1") (pintype "passive"))
      (node (ref "IC13") (pin "1") (pinfunction "VIN_1") (pintype "bidirectional"))
      (node (ref "R93") (pin "2") (pinfunction "2_2") (pintype "passive"))
    )
    (net (code "94") (name "Net-(IC16A-+IN)") (class "Default")
      (node (ref "C62") (pin "1") (pinfunction "1_1") (pintype "passive"))
      (node (ref "IC16") (pin "3") (pinfunction "+IN_3") (pintype "input"))
      (node (ref "R95") (pin "2") (pinfunction "2_2") (pintype "passive"))
      (node (ref "R96") (pin "1") (pinfunction "1_1") (pintype "passive"))
    )
    (net (code "95") (name "Net-(IC16A--IN)") (class "Default")
      (node (ref "IC16") (pin "1") (pinfunction "OUT_1") (pintype "output"))
      (node (ref "IC16") (pin "2") (pinfunction "-IN_2") (pintype "input"))
      (node (ref "R101") (pin "2") (pinfunction "2_2") (pintype "passive"))
    )
    (net (code "96") (name "Net-(IC16B-+IN)") (class "Default")
      (node (ref "C63") (pin "1") (pinfunction "1_1") (pintype "passive"))
      (node (ref "IC16") (pin "5") (pinfunction "+IN_5") (pintype "input"))
      (node (ref "R98") (pin "2") (pinfunction "2_2") (pintype "passive"))
      (node (ref "R99") (pin "1") (pinfunction "1_1") (pintype "passive"))
    )
    (net (code "97") (name "Net-(IC16B--IN)") (class "Default")
      (node (ref "IC16") (pin "6") (pinfunction "-IN_6") (pintype "input"))
      (node (ref "IC16") (pin "7") (pinfunction "OUT_7") (pintype "output"))
      (node (ref "R100") (pin "2") (pinfunction "2_2") (pintype "passive"))
    )
    (net (code "98") (name "Net-(IC16C-V+)") (class "Default")
      (node (ref "C67") (pin "1") (pinfunction "1_1") (pintype "passive"))
      (node (ref "IC16") (pin "8") (pinfunction "V+_8") (pintype "input"))
      (node (ref "R103") (pin "1") (pinfunction "1_1") (pintype "passive"))
    )
    (net (code "99") (name "Net-(J12-+5V)") (class "Default")
      (node (ref "C85") (pin "1") (pinfunction "1_1") (pintype "passive"))
      (node (ref "D6") (pin "A") (pinfunction "A_A") (pintype "passive"))
      (node (ref "IC15") (pin "4") (pinfunction "4_4") (pintype "input"))
      (node (ref "J12") (pin "1_+5V") (pinfunction "+5V_1_+5V") (pintype "bidirectional"))
      (node (ref "R128") (pin "1") (pinfunction "1_1") (pintype "passive"))
    )
    (net (code "100") (name "Net-(JP1-Pad1)") (class "Default")
      (node (ref "JP1") (pin "1") (pinfunction "1_1") (pintype "bidirectional"))
      (node (ref "R21") (pin "1") (pinfunction "1_1") (pintype "passive"))
    )
    (net (code "101") (name "Net-(L13-Pad2)") (class "Default")
      (node (ref "L13") (pin "2") (pinfunction "2_2") (pintype "passive"))
      (node (ref "R92") (pin "1") (pinfunction "1_1") (pintype "passive"))
    )
    (net (code "102") (name "Net-(Q1B-G)") (class "Default")
      (node (ref "C70") (pin "2") (pinfunction "2_2") (pintype "passive"))
      (node (ref "Q1") (pin "5") (pinfunction "G_5") (pintype "passive"))
      (node (ref "R75") (pin "1") (pinfunction "1_1") (pintype "passive"))
      (node (ref "R82") (pin "2") (pinfunction "2_2") (pintype "passive"))
    )
    (net (code "103") (name "Net-(Q1B-S)") (class "Default")
      (node (ref "Q1") (pin "4") (pinfunction "S_4") (pintype "passive"))
      (node (ref "R106") (pin "1") (pinfunction "1_1") (pintype "passive"))
    )
    (net (code "104") (name "Net-(Q2B-G)") (class "Default")
      (node (ref "C69") (pin "2") (pinfunction "2_2") (pintype "passive"))
      (node (ref "Q2") (pin "5") (pinfunction "G_5") (pintype "passive"))
      (node (ref "R24") (pin "1") (pinfunction "1_1") (pintype "passive"))
      (node (ref "R65") (pin "2") (pinfunction "2_2") (pintype "passive"))
    )
    (net (code "105") (name "Net-(Q2B-S)") (class "Default")
      (node (ref "Q2") (pin "4") (pinfunction "S_4") (pintype "passive"))
      (node (ref "R105") (pin "1") (pinfunction "1_1") (pintype "passive"))
    )
    (net (code "106") (name "Net-(Q3-Q2D1)") (class "Default")
      (node (ref "Q3") (pin "2") (pinfunction "Q2D1_2") (pintype "bidirectional"))
      (node (ref "Q3") (pin "3") (pinfunction "Q2D2_3") (pintype "bidirectional"))
      (node (ref "R6") (pin "1") (pinfunction "1_1") (pintype "passive"))
      (node (ref "R8") (pin "1") (pinfunction "1_1") (pintype "passive"))
    )
    (net (code "107") (name "Net-(Q3-Q2G)") (class "Default")
      (node (ref "Q3") (pin "6") (pinfunction "Q2G_6") (pintype "input"))
      (node (ref "R9") (pin "3") (pinfunction "1_3") (pintype "passive"))
    )
    (net (code "108") (name "Net-(Q4A-D)") (class "Default")
      (node (ref "C33") (pin "2") (pinfunction "2_2") (pintype "passive"))
      (node (ref "Q4") (pin "6") (pinfunction "D_6") (pintype "passive"))
      (node (ref "Q5") (pin "1") (pinfunction "G_1") (pintype "passive"))
      (node (ref "R42") (pin "2") (pinfunction "2_2") (pintype "passive"))
    )
    (net (code "109") (name "Net-(Q4A-S)") (class "Default")
      (node (ref "Q4") (pin "1") (pinfunction "S_1") (pintype "passive"))
      (node (ref "R40") (pin "2") (pinfunction "2_2") (pintype "passive"))
    )
    (net (code "110") (name "Net-(Q4B-D)") (class "Default")
      (node (ref "C34") (pin "2") (pinfunction "2_2") (pintype "passive"))
      (node (ref "Q4") (pin "3") (pinfunction "D_3") (pintype "passive"))
      (node (ref "Q5") (pin "3") (pinfunction "G_3") (pintype "passive"))
      (node (ref "R45") (pin "2") (pinfunction "2_2") (pintype "passive"))
    )
    (net (code "111") (name "Net-(Q4B-S)") (class "Default")
      (node (ref "Q4") (pin "4") (pinfunction "S_4") (pintype "passive"))
      (node (ref "R43") (pin "2") (pinfunction "2_2") (pintype "passive"))
    )
    (net (code "112") (name "Net-(Q5A-D)") (class "Default")
      (node (ref "F1") (pin "2") (pinfunction "2_2") (pintype "passive"))
      (node (ref "Q5") (pin "6") (pinfunction "D_6") (pintype "passive"))
      (node (ref "R35") (pin "1") (pinfunction "1_1") (pintype "passive"))
      (node (ref "R37") (pin "1") (pinfunction "1_1") (pintype "passive"))
      (node (ref "R97") (pin "1") (pinfunction "1_1") (pintype "passive"))
    )
    (net (code "113") (name "Net-(Q6A-D)") (class "Default")
      (node (ref "C8") (pin "2") (pinfunction "2_2") (pintype "passive"))
      (node (ref "Q6") (pin "6") (pinfunction "D_6") (pintype "passive"))
      (node (ref "Q7") (pin "1") (pinfunction "G_1") (pintype "passive"))
      (node (ref "R13") (pin "2") (pinfunction "2_2") (pintype "passive"))
    )
    (net (code "114") (name "Net-(Q6A-S)") (class "Default")
      (node (ref "Q6") (pin "1") (pinfunction "S_1") (pintype "passive"))
      (node (ref "R14") (pin "2") (pinfunction "2_2") (pintype "passive"))
    )
    (net (code "115") (name "Net-(R23-Pad1)") (class "Default")
      (node (ref "R23") (pin "1") (pinfunction "1_1") (pintype "passive"))
      (node (ref "R49") (pin "2") (pinfunction "2_2") (pintype "passive"))
    )
    (net (code "116") (name "Net-(R35-Pad2)") (class "Default")
      (node (ref "R35") (pin "2") (pinfunction "2_2") (pintype "passive"))
      (node (ref "R36") (pin "1") (pinfunction "1_1") (pintype "passive"))
      (node (ref "R37") (pin "2") (pinfunction "2_2") (pintype "passive"))
      (node (ref "R38") (pin "1") (pinfunction "1_1") (pintype "passive"))
    )
    (net (code "117") (name "Net-(R94-Pad2)") (class "Default")
      (node (ref "R94") (pin "2") (pinfunction "2_2") (pintype "passive"))
      (node (ref "R95") (pin "1") (pinfunction "1_1") (pintype "passive"))
    )
    (net (code "118") (name "Net-(R97-Pad2)") (class "Default")
      (node (ref "R97") (pin "2") (pinfunction "2_2") (pintype "passive"))
      (node (ref "R98") (pin "1") (pinfunction "1_1") (pintype "passive"))
    )
    (net (code "119") (name "PGND") (class "Default")
      (node (ref "C1") (pin "2") (pinfunction "2_2") (pintype "passive"))
      (node (ref "C12") (pin "2") (pinfunction "2_2") (pintype "passive"))
      (node (ref "C3") (pin "2") (pinfunction "2_2") (pintype "passive"))
      (node (ref "C38") (pin "2") (pinfunction "2_2") (pintype "passive"))
      (node (ref "C4") (pin "2") (pinfunction "2_2") (pintype "passive"))
      (node (ref "C43") (pin "2") (pinfunction "2_2") (pintype "passive"))
      (node (ref "C44") (pin "2") (pinfunction "2_2") (pintype "passive"))
      (node (ref "C5") (pin "2") (pinfunction "2_2") (pintype "passive"))
      (node (ref "C6") (pin "2") (pinfunction "2_2") (pintype "passive"))
      (node (ref "C7") (pin "2") (pinfunction "2_2") (pintype "passive"))
      (node (ref "D8") (pin "A") (pinfunction "A_A") (pintype "passive"))
      (node (ref "D9") (pin "1") (pinfunction "A_1") (pintype "passive"))
      (node (ref "IC2") (pin "1") (pinfunction "GND1_1") (pintype "input"))
      (node (ref "IC2") (pin "2") (pinfunction "GND2_2") (pintype "input"))
      (node (ref "IC2") (pin "21") (pinfunction "GND21_21") (pintype "input"))
      (node (ref "IC2") (pin "3") (pinfunction "GND3_3") (pintype "input"))
      (node (ref "IC2") (pin "4") (pinfunction "GND4_4") (pintype "input"))
      (node (ref "IC2") (pin "5") (pinfunction "GND5_5") (pintype "input"))
      (node (ref "IC2") (pin "6") (pinfunction "GND6_6") (pintype "input"))
      (node (ref "IC2") (pin "7") (pinfunction "GND7_7") (pintype "input"))
      (node (ref "IC2") (pin "8") (pinfunction "GND8_8") (pintype "input"))
      (node (ref "IC2") (pin "G") (pinfunction "GNEXP_G") (pintype "input"))
      (node (ref "J14") (pin "5") (pinfunction "5_5") (pintype "passive"))
      (node (ref "J15") (pin "5") (pinfunction "5_5") (pintype "passive"))
      (node (ref "L2") (pin "1") (pinfunction "1_1") (pintype "passive"))
      (node (ref "Q3") (pin "1") (pinfunction "Q1S_1") (pintype "bidirectional"))
      (node (ref "R1") (pin "2") (pinfunction "1_2") (pintype "passive"))
      (node (ref "R1") (pin "4") (pinfunction "1_4") (pintype "passive"))
      (node (ref "R10") (pin "1") (pinfunction "1_1") (pintype "passive"))
      (node (ref "R10") (pin "2") (pinfunction "1_2") (pintype "passive"))
      (node (ref "R10") (pin "3") (pinfunction "1_3") (pintype "passive"))
      (node (ref "R10") (pin "4") (pinfunction "1_4") (pintype "passive"))
      (node (ref "R11") (pin "7") (pinfunction "2_7") (pintype "passive"))
      (node (ref "R11") (pin "8") (pinfunction "2_8") (pintype "passive"))
      (node (ref "R3") (pin "1") (pinfunction "1_1") (pintype "passive"))
      (node (ref "R4") (pin "1") (pinfunction "1_1") (pintype "passive"))
      (node (ref "R5") (pin "1") (pinfunction "1_1") (pintype "passive"))
      (node (ref "R50") (pin "5") (pinfunction "2_5") (pintype "passive"))
      (node (ref "R50") (pin "6") (pinfunction "2_6") (pintype "passive"))
      (node (ref "R9") (pin "2") (pinfunction "1_2") (pintype "passive"))
    )
    (net (code "120") (name "VACT") (class "Default")
      (node (ref "C1") (pin "1") (pinfunction "1_1") (pintype "passive"))
      (node (ref "C37") (pin "1") (pinfunction "1_1") (pintype "passive"))
      (node (ref "C38") (pin "1") (pinfunction "1_1") (pintype "passive"))
      (node (ref "D1") (pin "1") (pinfunction "A_1") (pintype "passive"))
      (node (ref "D8") (pin "C") (pinfunction "C_C") (pintype "passive"))
      (node (ref "IC2") (pin "20") (pinfunction "VS_B_20") (pintype "input"))
      (node (ref "IC2") (pin "22") (pinfunction "VS_A_22") (pintype "input"))
      (node (ref "Q7") (pin "6") (pinfunction "D_6") (pintype "passive"))
      (node (ref "R7") (pin "3") (pinfunction "1_3") (pintype "passive"))
    )
    (net (code "121") (name "VBAT") (class "Default")
      (node (ref "C22") (pin "1") (pinfunction "1_1") (pintype "passive"))
      (node (ref "C23") (pin "1") (pinfunction "1_1") (pintype "passive"))
      (node (ref "C8") (pin "1") (pinfunction "1_1") (pintype "passive"))
      (node (ref "C83") (pin "1") (pinfunction "1_1") (pintype "passive"))
      (node (ref "C84") (pin "1") (pinfunction "1_1") (pintype "passive"))
      (node (ref "IC10") (pin "4") (pinfunction "VIN-_4") (pintype "input"))
      (node (ref "IC3") (pin "4") (pinfunction "VIN_4") (pintype "input"))
      (node (ref "JP1") (pin "3") (pinfunction "3_3") (pintype "bidirectional"))
      (node (ref "Q3") (pin "4") (pinfunction "Q2S_4") (pintype "bidirectional"))
      (node (ref "Q7") (pin "5") (pinfunction "S_5") (pintype "passive"))
      (node (ref "R13") (pin "1") (pinfunction "1_1") (pintype "passive"))
      (node (ref "R22") (pin "1") (pinfunction "1_1") (pintype "passive"))
      (node (ref "R33") (pin "2") (pinfunction "2_2") (pintype "passive"))
      (node (ref "R39") (pin "1") (pinfunction "1_1") (pintype "passive"))
      (node (ref "R9") (pin "6") (pinfunction "2_6") (pintype "passive"))
    )
    (net (code "122") (name "unconnected-(IC1-AN8{slash}RPB8{slash}CTED10{slash}RB8-Pad32)") (class "Default")
      (node (ref "IC1") (pin "32") (pinfunction "AN8/RPB8/CTED10/RB8_32") (pintype "bidirectional"))
    )
    (net (code "123") (name "unconnected-(IC1-AN9{slash}RPB9{slash}CTED4{slash}RB9-Pad33)") (class "Default")
      (node (ref "IC1") (pin "33") (pinfunction "AN9/RPB9/CTED4/RB9_33") (pintype "bidirectional"))
    )
    (net (code "124") (name "unconnected-(IC1-AN11{slash}PMA12{slash}RB11-Pad35)") (class "Default")
      (node (ref "IC1") (pin "35") (pinfunction "AN11/PMA12/RB11_35") (pintype "bidirectional"))
    )
    (net (code "125") (name "unconnected-(IC1-AN12{slash}PMA11{slash}RB12-Pad41)") (class "Default")
      (node (ref "IC1") (pin "41") (pinfunction "AN12/PMA11/RB12_41") (pintype "bidirectional"))
    )
    (net (code "126") (name "unconnected-(IC1-AN13{slash}RB13-Pad42)") (class "Default")
      (node (ref "IC1") (pin "42") (pinfunction "AN13/RB13_42") (pintype "bidirectional"))
    )
    (net (code "127") (name "unconnected-(IC1-AN14{slash}RPB14{slash}PMA1{slash}CTED5{slash}RB14-Pad43)") (class "Default")
      (node (ref "IC1") (pin "43") (pinfunction "AN14/RPB14/PMA1/CTED5/RB14_43") (pintype "bidirectional"))
    )
    (net (code "128") (name "unconnected-(IC1-AN15{slash}RPB15{slash}PMA0{slash}CTED6{slash}{slash}RB15-Pad44)") (class "Default")
      (node (ref "IC1") (pin "44") (pinfunction "AN15/RPB15/PMA0/CTED6//RB15_44") (pintype "bidirectional"))
    )
    (net (code "129") (name "unconnected-(IC1-AN20{slash}PMD2{slash}RE2-Pad98)") (class "Default")
      (node (ref "IC1") (pin "98") (pinfunction "AN20/PMD2/RE2_98") (pintype "bidirectional"))
    )
    (net (code "130") (name "unconnected-(IC1-AN21{slash}PMD4{slash}RE4-Pad100)") (class "Default")
      (node (ref "IC1") (pin "100") (pinfunction "AN21/PMD4/RE4_100") (pintype "bidirectional"))
    )
    (net (code "131") (name "unconnected-(IC1-AN22{slash}RPE5{slash}PMD5{slash}RE5-Pad3)") (class "Default")
      (node (ref "IC1") (pin "3") (pinfunction "AN22/RPE5/PMD5/RE5_3") (pintype "bidirectional"))
    )
    (net (code "132") (name "unconnected-(IC1-AN23{slash}PMD6{slash}RE6-Pad4)") (class "Default")
      (node (ref "IC1") (pin "4") (pinfunction "AN23/PMD6/RE6_4") (pintype "bidirectional"))
    )
    (net (code "133") (name "unconnected-(IC1-AN24{slash}RPD1{slash}RD1-Pad76)") (class "Default")
      (node (ref "IC1") (pin "76") (pinfunction "AN24/RPD1/RD1_76") (pintype "bidirectional"))
    )
    (net (code "134") (name "unconnected-(IC1-AN25{slash}RPD2{slash}RD2-Pad77)") (class "Default")
      (node (ref "IC1") (pin "77") (pinfunction "AN25/RPD2/RD2_77") (pintype "bidirectional"))
    )
    (net (code "135") (name "unconnected-(IC1-AN26{slash}RPD3{slash}RD3-Pad78)") (class "Default")
      (node (ref "IC1") (pin "78") (pinfunction "AN26/RPD3/RD3_78") (pintype "bidirectional"))
    )
    (net (code "136") (name "unconnected-(IC1-AN27{slash}PMD7{slash}RE7-Pad5)") (class "Default")
      (node (ref "IC1") (pin "5") (pinfunction "AN27/PMD7/RE7_5") (pintype "bidirectional"))
    )
    (net (code "137") (name "unconnected-(IC1-CVREFOUT{slash}AN10{slash}RPB10{slash}PMA13{slash}CTED11{slash}RB10-Pad34)") (class "Default")
      (node (ref "IC1") (pin "34") (pinfunction "CVREFOUT/AN10/RPB10/PMA13/CTED11/RB10_34") (pintype "bidirectional"))
    )
    (net (code "138") (name "unconnected-(IC1-PGEC3{slash}AN2{slash}C2INB{slash}RPB2{slash}CTED13{slash}RB2-Pad23)") (class "Default")
      (node (ref "IC1") (pin "23") (pinfunction "PGEC3/AN2/C2INB/RPB2/CTED13/RB2_23") (pintype "bidirectional"))
    )
    (net (code "139") (name "unconnected-(IC1-PMD0{slash}RE0-Pad93)") (class "Default")
      (node (ref "IC1") (pin "93") (pinfunction "PMD0/RE0_93") (pintype "bidirectional"))
    )
    (net (code "140") (name "unconnected-(IC1-PMD1{slash}RE1-Pad94)") (class "Default")
      (node (ref "IC1") (pin "94") (pinfunction "PMD1/RE1_94") (pintype "bidirectional"))
    )
    (net (code "141") (name "unconnected-(IC1-PMD13{slash}RD13-Pad80)") (class "Default")
      (node (ref "IC1") (pin "80") (pinfunction "PMD13/RD13_80") (pintype "bidirectional"))
    )
    (net (code "142") (name "unconnected-(IC1-PMD14{slash}RD6-Pad83)") (class "Default")
      (node (ref "IC1") (pin "83") (pinfunction "PMD14/RD6_83") (pintype "bidirectional"))
    )
    (net (code "143") (name "unconnected-(IC1-RPC1{slash}RC1-Pad6)") (class "Default")
      (node (ref "IC1") (pin "6") (pinfunction "RPC1/RC1_6") (pintype "bidirectional"))
    )
    (net (code "144") (name "unconnected-(IC1-RPC2{slash}RC2-Pad7)") (class "Default")
      (node (ref "IC1") (pin "7") (pinfunction "RPC2/RC2_7") (pintype "bidirectional"))
    )
    (net (code "145") (name "unconnected-(IC1-RPC3{slash}RC3-Pad8)") (class "Default")
      (node (ref "IC1") (pin "8") (pinfunction "RPC3/RC3_8") (pintype "bidirectional"))
    )
    (net (code "146") (name "unconnected-(IC1-RPD0{slash}INT0{slash}RD0-Pad72)") (class "Default")
      (node (ref "IC1") (pin "72") (pinfunction "RPD0/INT0/RD0_72") (pintype "bidirectional"))
    )
    (net (code "147") (name "unconnected-(IC1-RPD4{slash}PMWR{slash}RD4-Pad81)") (class "Default")
      (node (ref "IC1") (pin "81") (pinfunction "RPD4/PMWR/RD4_81") (pintype "bidirectional"))
    )
    (net (code "148") (name "unconnected-(IC1-RPD5{slash}PMRD{slash}RD5-Pad82)") (class "Default")
      (node (ref "IC1") (pin "82") (pinfunction "RPD5/PMRD/RD5_82") (pintype "bidirectional"))
    )
    (net (code "149") (name "unconnected-(IC1-RPD8{slash}RTCC{slash}RD8-Pad68)") (class "Default")
      (node (ref "IC1") (pin "68") (pinfunction "RPD8/RTCC/RD8_68") (pintype "bidirectional"))
    )
    (net (code "150") (name "unconnected-(IC1-RPD9{slash}RD9-Pad69)") (class "Default")
      (node (ref "IC1") (pin "69") (pinfunction "RPD9/RD9_69") (pintype "bidirectional"))
    )
    (net (code "151") (name "unconnected-(IC1-RPD10{slash}SCK1{slash}PMCS2{slash}RD10-Pad70)") (class "Default")
      (node (ref "IC1") (pin "70") (pinfunction "RPD10/SCK1/PMCS2/RD10_70") (pintype "bidirectional"))
    )
    (net (code "152") (name "unconnected-(IC1-RPD11{slash}PMCS1{slash}RD11-Pad71)") (class "Default")
      (node (ref "IC1") (pin "71") (pinfunction "RPD11/PMCS1/RD11_71") (pintype "bidirectional"))
    )
    (net (code "153") (name "unconnected-(IC1-RPD12{slash}PMD12{slash}RD12-Pad79)") (class "Default")
      (node (ref "IC1") (pin "79") (pinfunction "RPD12/PMD12/RD12_79") (pintype "bidirectional"))
    )
    (net (code "154") (name "unconnected-(IC1-RPD14{slash}RD14-Pad47)") (class "Default")
      (node (ref "IC1") (pin "47") (pinfunction "RPD14/RD14_47") (pintype "bidirectional"))
    )
    (net (code "155") (name "unconnected-(IC1-RPD15{slash}RD15-Pad48)") (class "Default")
      (node (ref "IC1") (pin "48") (pinfunction "RPD15/RD15_48") (pintype "bidirectional"))
    )
    (net (code "156") (name "unconnected-(IC1-RPE3{slash}PMD3{slash}RE3-Pad99)") (class "Default")
      (node (ref "IC1") (pin "99") (pinfunction "RPE3/PMD3/RE3_99") (pintype "bidirectional"))
    )
    (net (code "157") (name "unconnected-(IC1-RPE8{slash}RE8-Pad18)") (class "Default")
      (node (ref "IC1") (pin "18") (pinfunction "RPE8/RE8_18") (pintype "bidirectional"))
    )
    (net (code "158") (name "unconnected-(IC1-RPE9{slash}RE9-Pad19)") (class "Default")
      (node (ref "IC1") (pin "19") (pinfunction "RPE9/RE9_19") (pintype "bidirectional"))
    )
    (net (code "159") (name "unconnected-(IC1-RPF3{slash}USBID{slash}RF3-Pad51)") (class "Default")
      (node (ref "IC1") (pin "51") (pinfunction "RPF3/USBID/RF3_51") (pintype "bidirectional"))
    )
    (net (code "160") (name "unconnected-(IC1-RPF4{slash}PMA9{slash}RF4-Pad49)") (class "Default")
      (node (ref "IC1") (pin "49") (pinfunction "RPF4/PMA9/RF4_49") (pintype "bidirectional"))
    )
    (net (code "161") (name "unconnected-(IC1-RPF5{slash}PMA8{slash}RF5-Pad50)") (class "Default")
      (node (ref "IC1") (pin "50") (pinfunction "RPF5/PMA8/RF5_50") (pintype "bidirectional"))
    )
    (net (code "162") (name "unconnected-(IC1-RPF12{slash}RF12-Pad40)") (class "Default")
      (node (ref "IC1") (pin "40") (pinfunction "RPF12/RF12_40") (pintype "bidirectional"))
    )
    (net (code "163") (name "unconnected-(IC1-RPF13{slash}RF13-Pad39)") (class "Default")
      (node (ref "IC1") (pin "39") (pinfunction "RPF13/RF13_39") (pintype "bidirectional"))
    )
    (net (code "164") (name "unconnected-(IC1-RPG0{slash}PMD8{slash}RG0-Pad90)") (class "Default")
      (node (ref "IC1") (pin "90") (pinfunction "RPG0/PMD8/RG0_90") (pintype "bidirectional"))
    )
    (net (code "165") (name "unconnected-(IC1-RPG1{slash}PMD9{slash}RG1-Pad89)") (class "Default")
      (node (ref "IC1") (pin "89") (pinfunction "RPG1/PMD9/RG1_89") (pintype "bidirectional"))
    )
    (net (code "166") (name "unconnected-(IC1-SCL2{slash}RA2-Pad58)") (class "Default")
      (node (ref "IC1") (pin "58") (pinfunction "SCL2/RA2_58") (pintype "bidirectional"))
    )
    (net (code "167") (name "unconnected-(IC1-SDA2{slash}RA3-Pad59)") (class "Default")
      (node (ref "IC1") (pin "59") (pinfunction "SDA2/RA3_59") (pintype "bidirectional"))
    )
    (net (code "168") (name "unconnected-(IC1-SOSCI{slash}RPC13{slash}RC13-Pad73)") (class "Default")
      (node (ref "IC1") (pin "73") (pinfunction "SOSCI/RPC13/RC13_73") (pintype "bidirectional"))
    )
    (net (code "169") (name "unconnected-(IC1-SOSCO{slash}RPC14{slash}T1CK{slash}RC14-Pad74)") (class "Default")
      (node (ref "IC1") (pin "74") (pinfunction "SOSCO/RPC14/T1CK/RC14_74") (pintype "bidirectional"))
    )
    (net (code "170") (name "unconnected-(IC1-TCK{slash}CTED2{slash}RA1-Pad38)") (class "Default")
      (node (ref "IC1") (pin "38") (pinfunction "TCK/CTED2/RA1_38") (pintype "bidirectional"))
    )
    (net (code "171") (name "unconnected-(IC1-TDI{slash}CTED9{slash}RA4-Pad60)") (class "Default")
      (node (ref "IC1") (pin "60") (pinfunction "TDI/CTED9/RA4_60") (pintype "bidirectional"))
    )
    (net (code "172") (name "unconnected-(IC1-TDO{slash}RA5-Pad61)") (class "Default")
      (node (ref "IC1") (pin "61") (pinfunction "TDO/RA5_61") (pintype "bidirectional"))
    )
    (net (code "173") (name "unconnected-(IC1-TMS{slash}CTED1{slash}RA0-Pad17)") (class "Default")
      (node (ref "IC1") (pin "17") (pinfunction "TMS/CTED1/RA0_17") (pintype "bidirectional"))
    )
    (net (code "174") (name "unconnected-(IC1-TRCLK{slash}RA6-Pad91)") (class "Default")
      (node (ref "IC1") (pin "91") (pinfunction "TRCLK/RA6_91") (pintype "bidirectional"))
    )
    (net (code "175") (name "unconnected-(IC1-TRD0{slash}RG13-Pad97)") (class "Default")
      (node (ref "IC1") (pin "97") (pinfunction "TRD0/RG13_97") (pintype "bidirectional"))
    )
    (net (code "176") (name "unconnected-(IC1-TRD2{slash}RG14-Pad95)") (class "Default")
      (node (ref "IC1") (pin "95") (pinfunction "TRD2/RG14_95") (pintype "bidirectional"))
    )
    (net (code "177") (name "unconnected-(IC1-TRD3{slash}CTED8{slash}RA7-Pad92)") (class "Default")
      (node (ref "IC1") (pin "92") (pinfunction "TRD3/CTED8/RA7_92") (pintype "bidirectional"))
    )
    (net (code "178") (name "unconnected-(IC3-PG-Pad9)") (class "Default")
      (node (ref "IC3") (pin "9") (pinfunction "PG_9") (pintype "bidirectional"))
    )
    (net (code "179") (name "unconnected-(Q1A-D-Pad6)") (class "Default")
      (node (ref "Q1") (pin "6") (pinfunction "D_6") (pintype "passive"))
    )
    (net (code "180") (name "unconnected-(Q1A-D1-PadP1)") (class "Default")
      (node (ref "Q1") (pin "P1") (pinfunction "D1_P1") (pintype "passive"))
    )
    (net (code "181") (name "unconnected-(Q1A-G-Pad2)") (class "Default")
      (node (ref "Q1") (pin "2") (pinfunction "G_2") (pintype "passive"))
    )
    (net (code "182") (name "unconnected-(Q1A-S-Pad1)") (class "Default")
      (node (ref "Q1") (pin "1") (pinfunction "S_1") (pintype "passive"))
    )
    (net (code "183") (name "unconnected-(Q2A-D-Pad6)") (class "Default")
      (node (ref "Q2") (pin "6") (pinfunction "D_6") (pintype "passive"))
    )
    (net (code "184") (name "unconnected-(Q2A-D1-PadP1)") (class "Default")
      (node (ref "Q2") (pin "P1") (pinfunction "D1_P1") (pintype "passive"))
    )
    (net (code "185") (name "unconnected-(Q2A-G-Pad2)") (class "Default")
      (node (ref "Q2") (pin "2") (pinfunction "G_2") (pintype "passive"))
    )
    (net (code "186") (name "unconnected-(Q2A-S-Pad1)") (class "Default")
      (node (ref "Q2") (pin "1") (pinfunction "S_1") (pintype "passive"))
    )
    (net (code "187") (name "unconnected-(Q6B-D-Pad3)") (class "Default")
      (node (ref "Q6") (pin "3") (pinfunction "D_3") (pintype "passive"))
    )
    (net (code "188") (name "unconnected-(Q6B-G-Pad5)") (class "Default")
      (node (ref "Q6") (pin "5") (pinfunction "G_5") (pintype "passive"))
    )
    (net (code "189") (name "unconnected-(Q6B-S-Pad4)") (class "Default")
      (node (ref "Q6") (pin "4") (pinfunction "S_4") (pintype "passive"))
    )
  )
)
